# wio_terminal.net
KiCad netlist of a schematic drawn in EAGLE
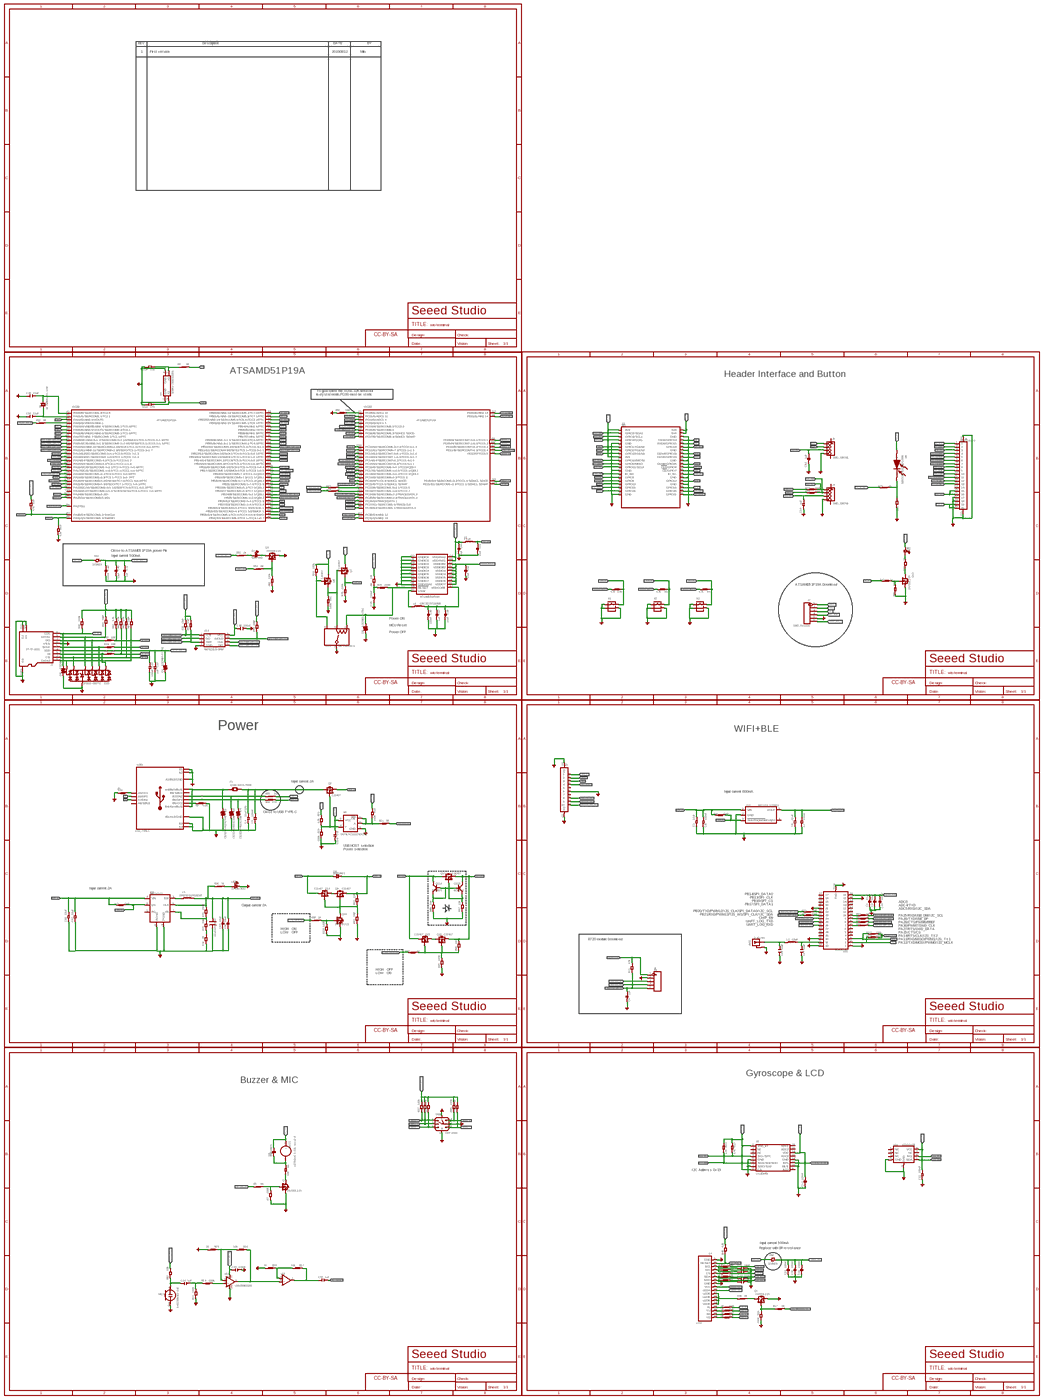
[diagram p0: schematic, sheet 1, overview]
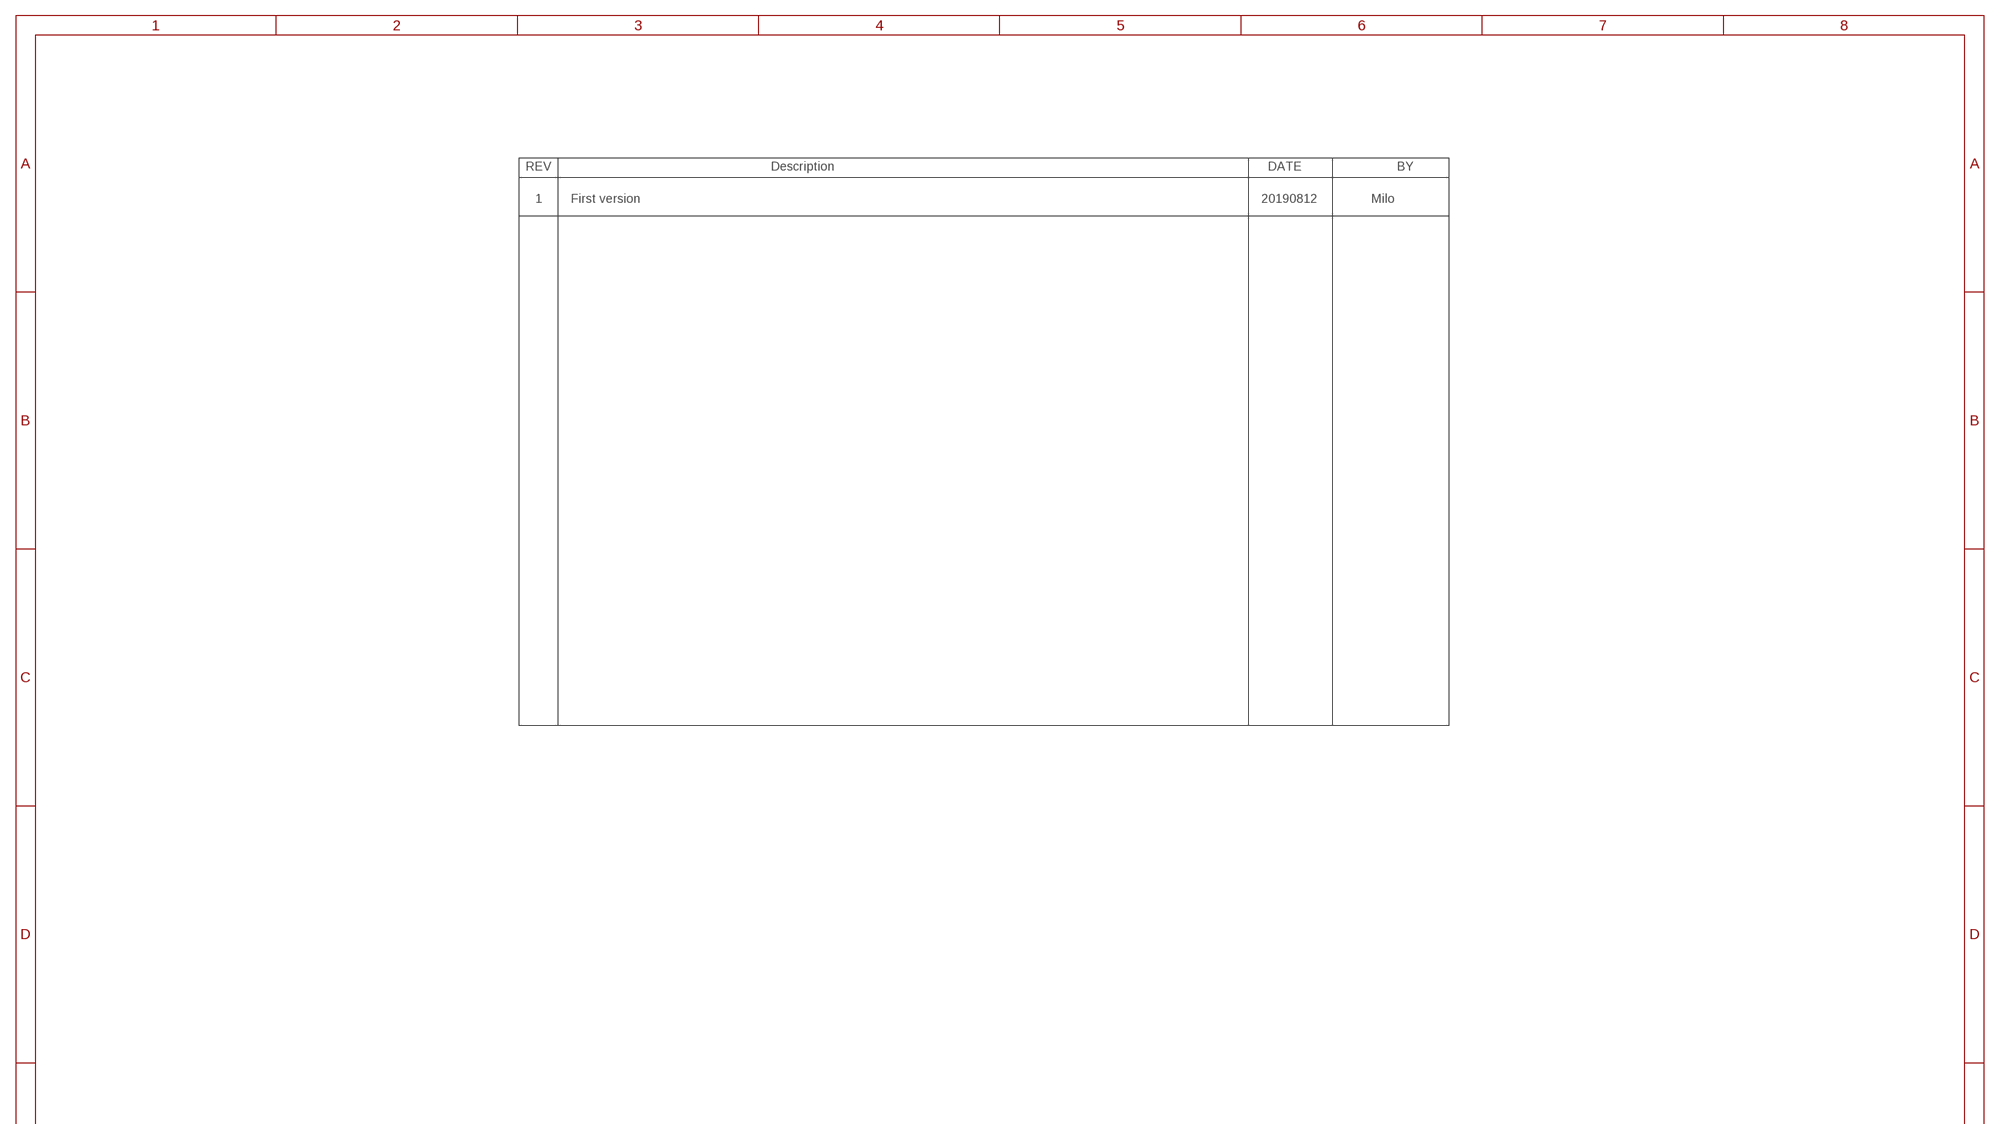
[diagram p1: schematic, sheet 1, part 1 of 7]
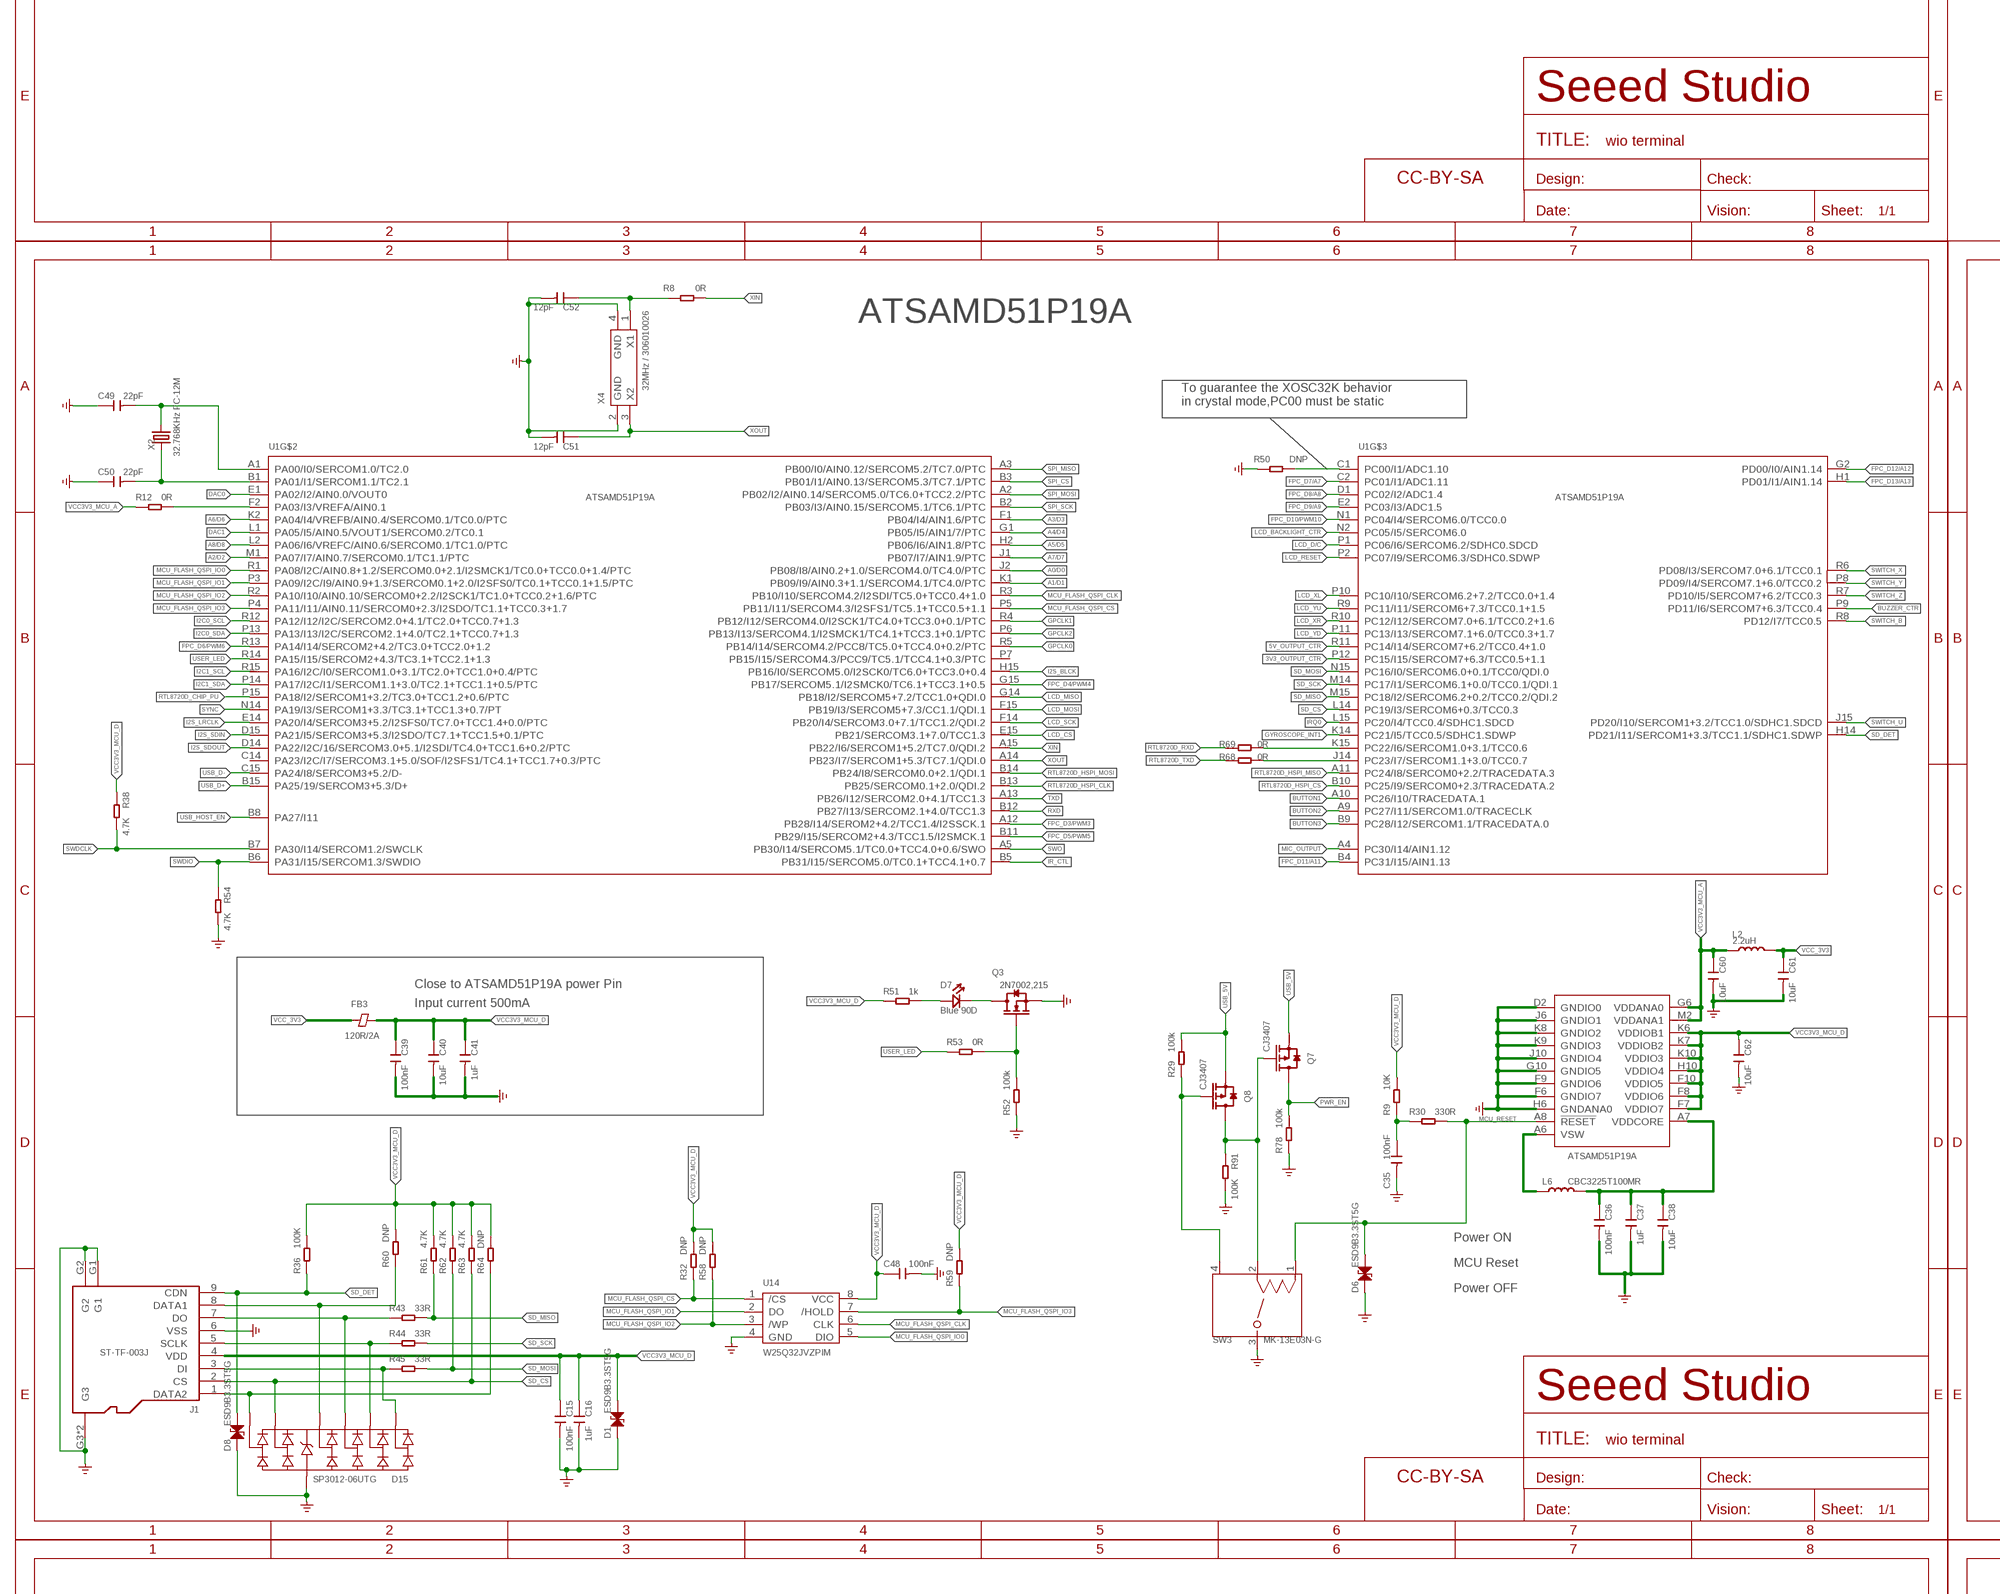
[diagram p2: schematic, sheet 1, part 2 of 7]
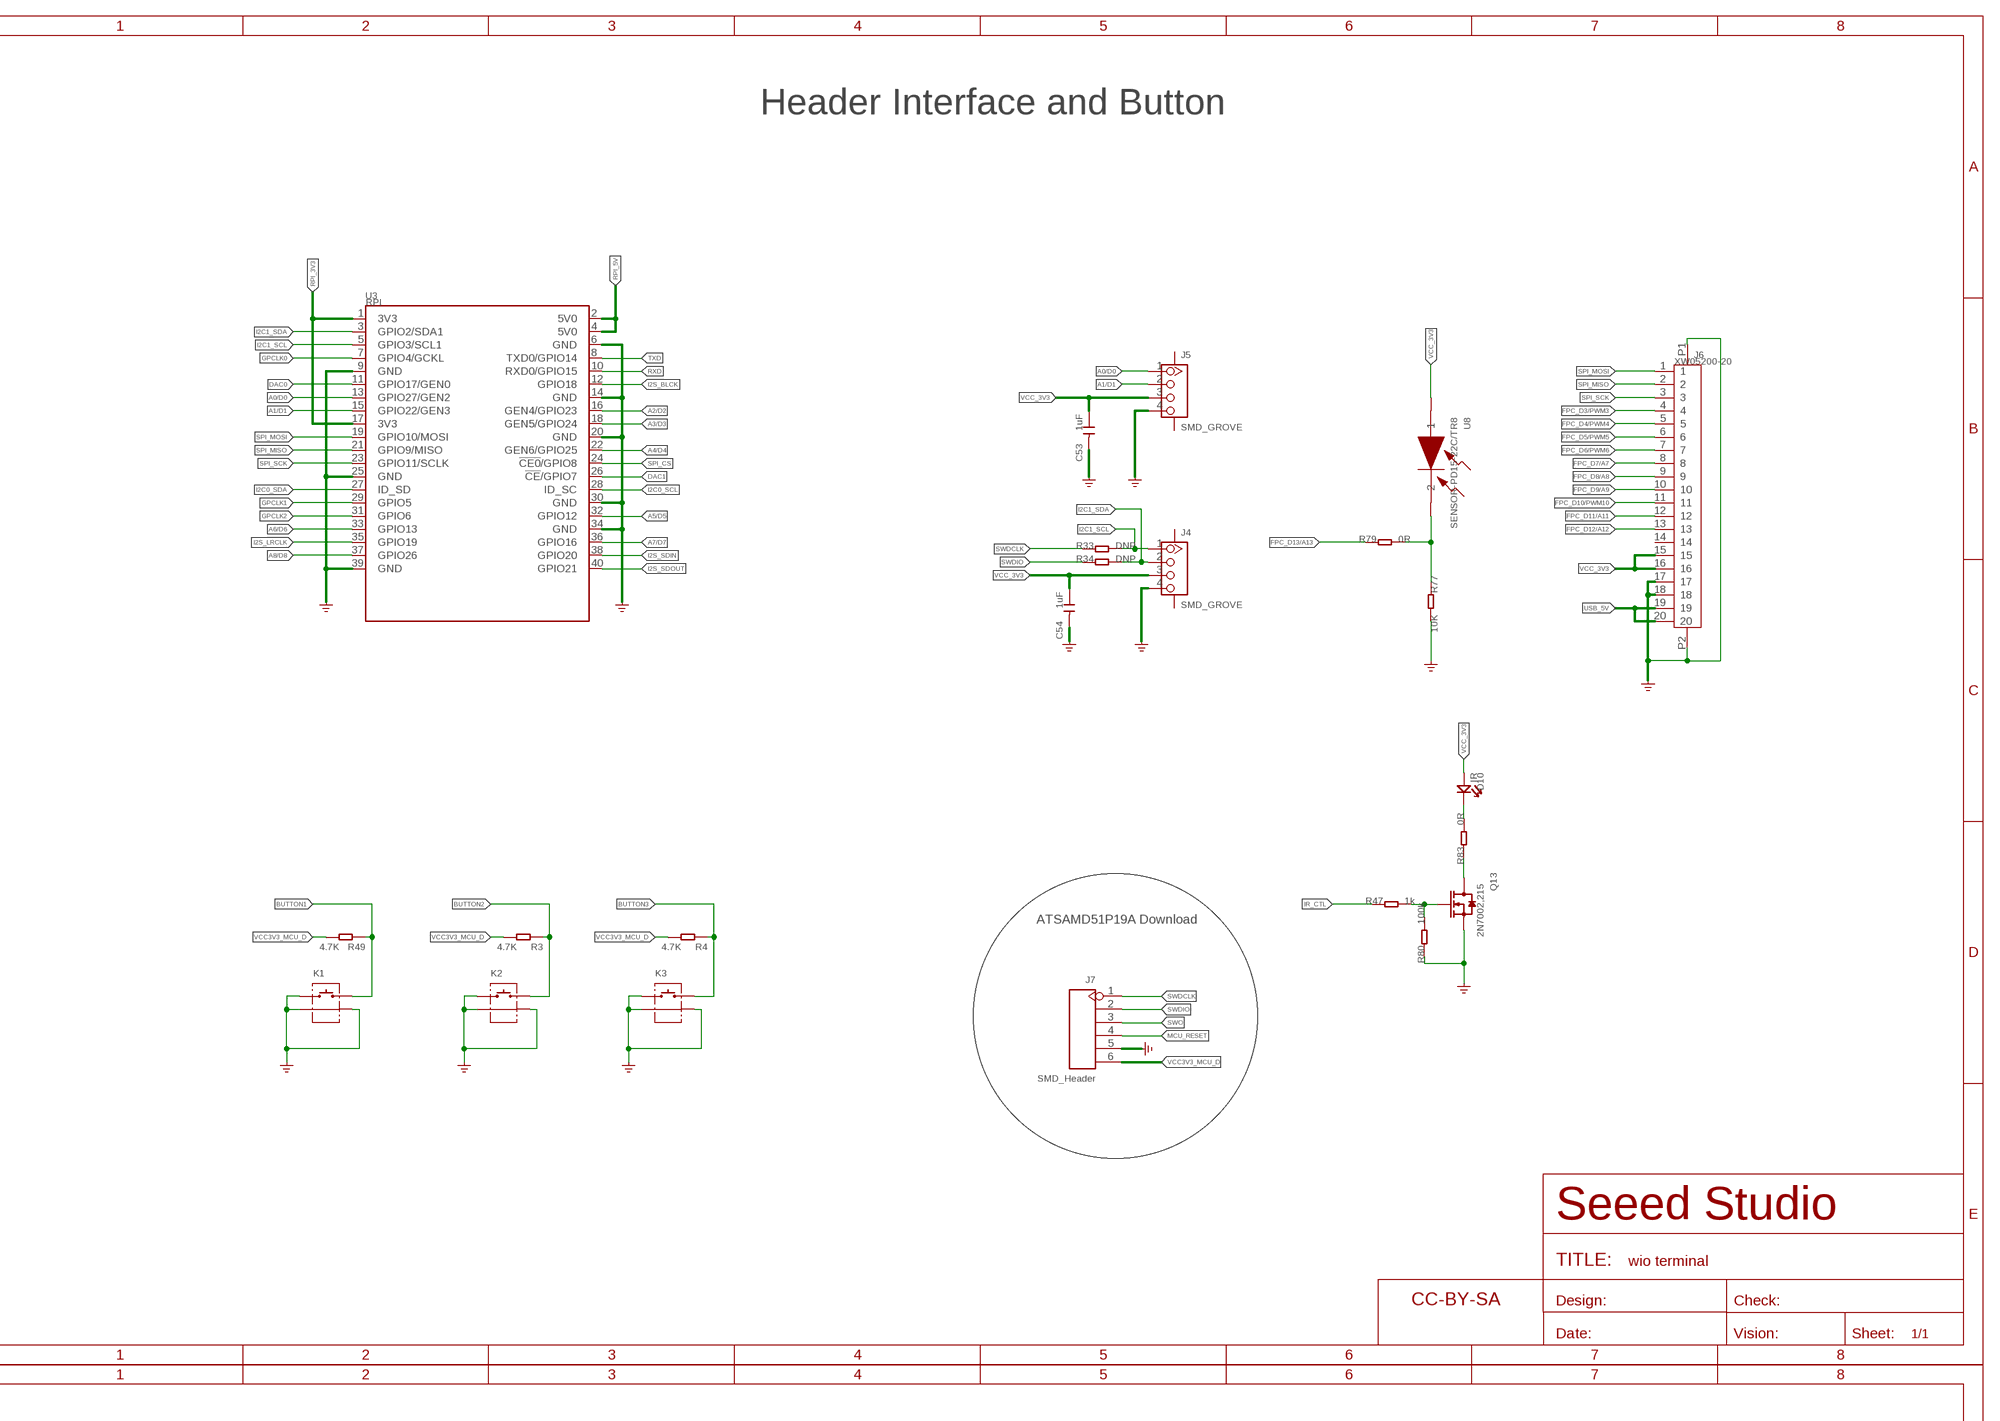
[diagram p3: schematic, sheet 1, part 3 of 7]
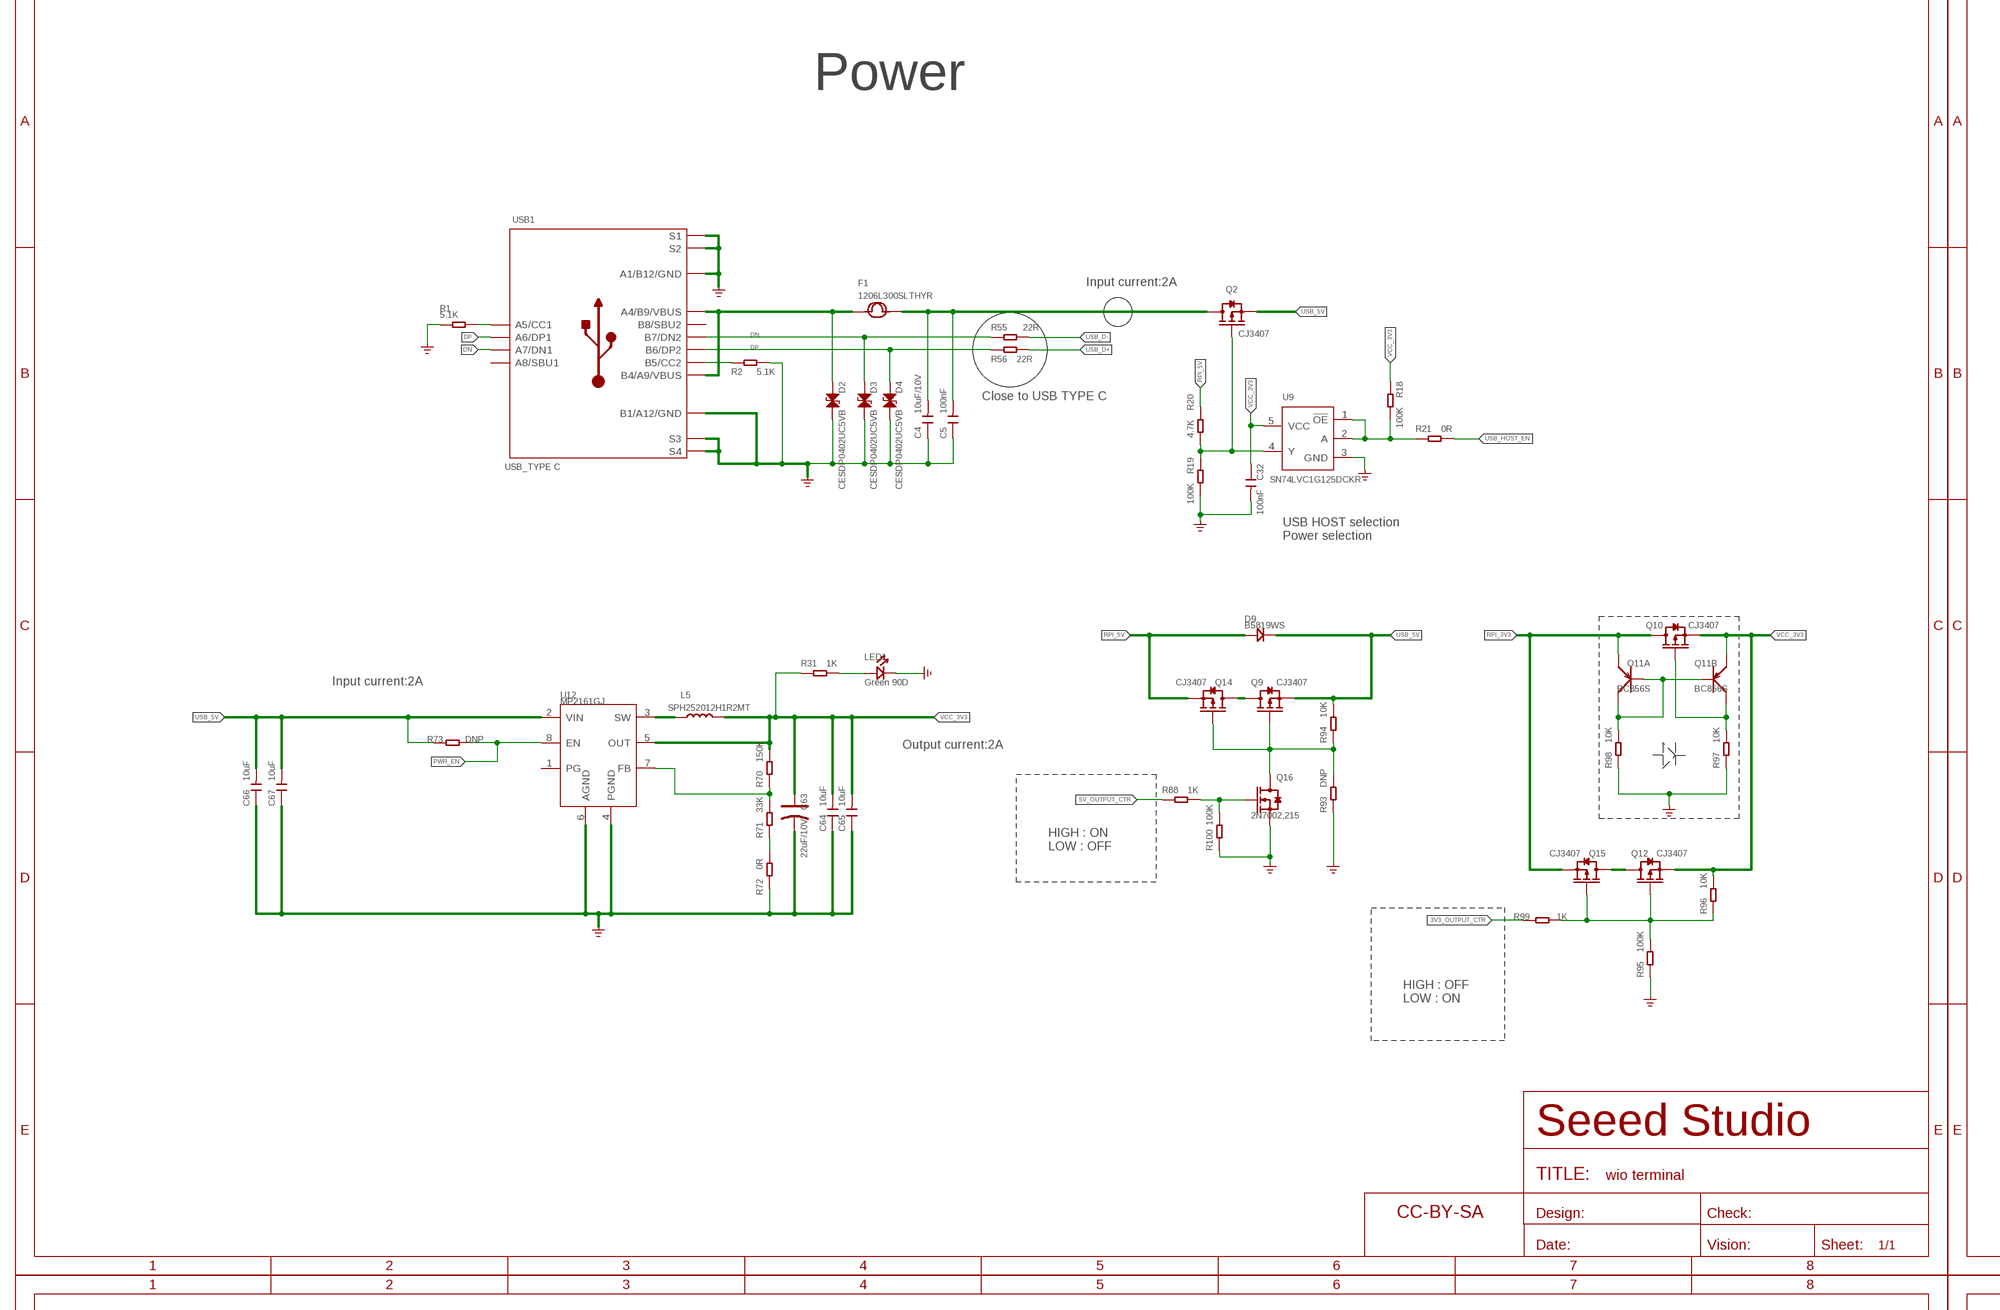
[diagram p4: schematic, sheet 1, part 4 of 7]
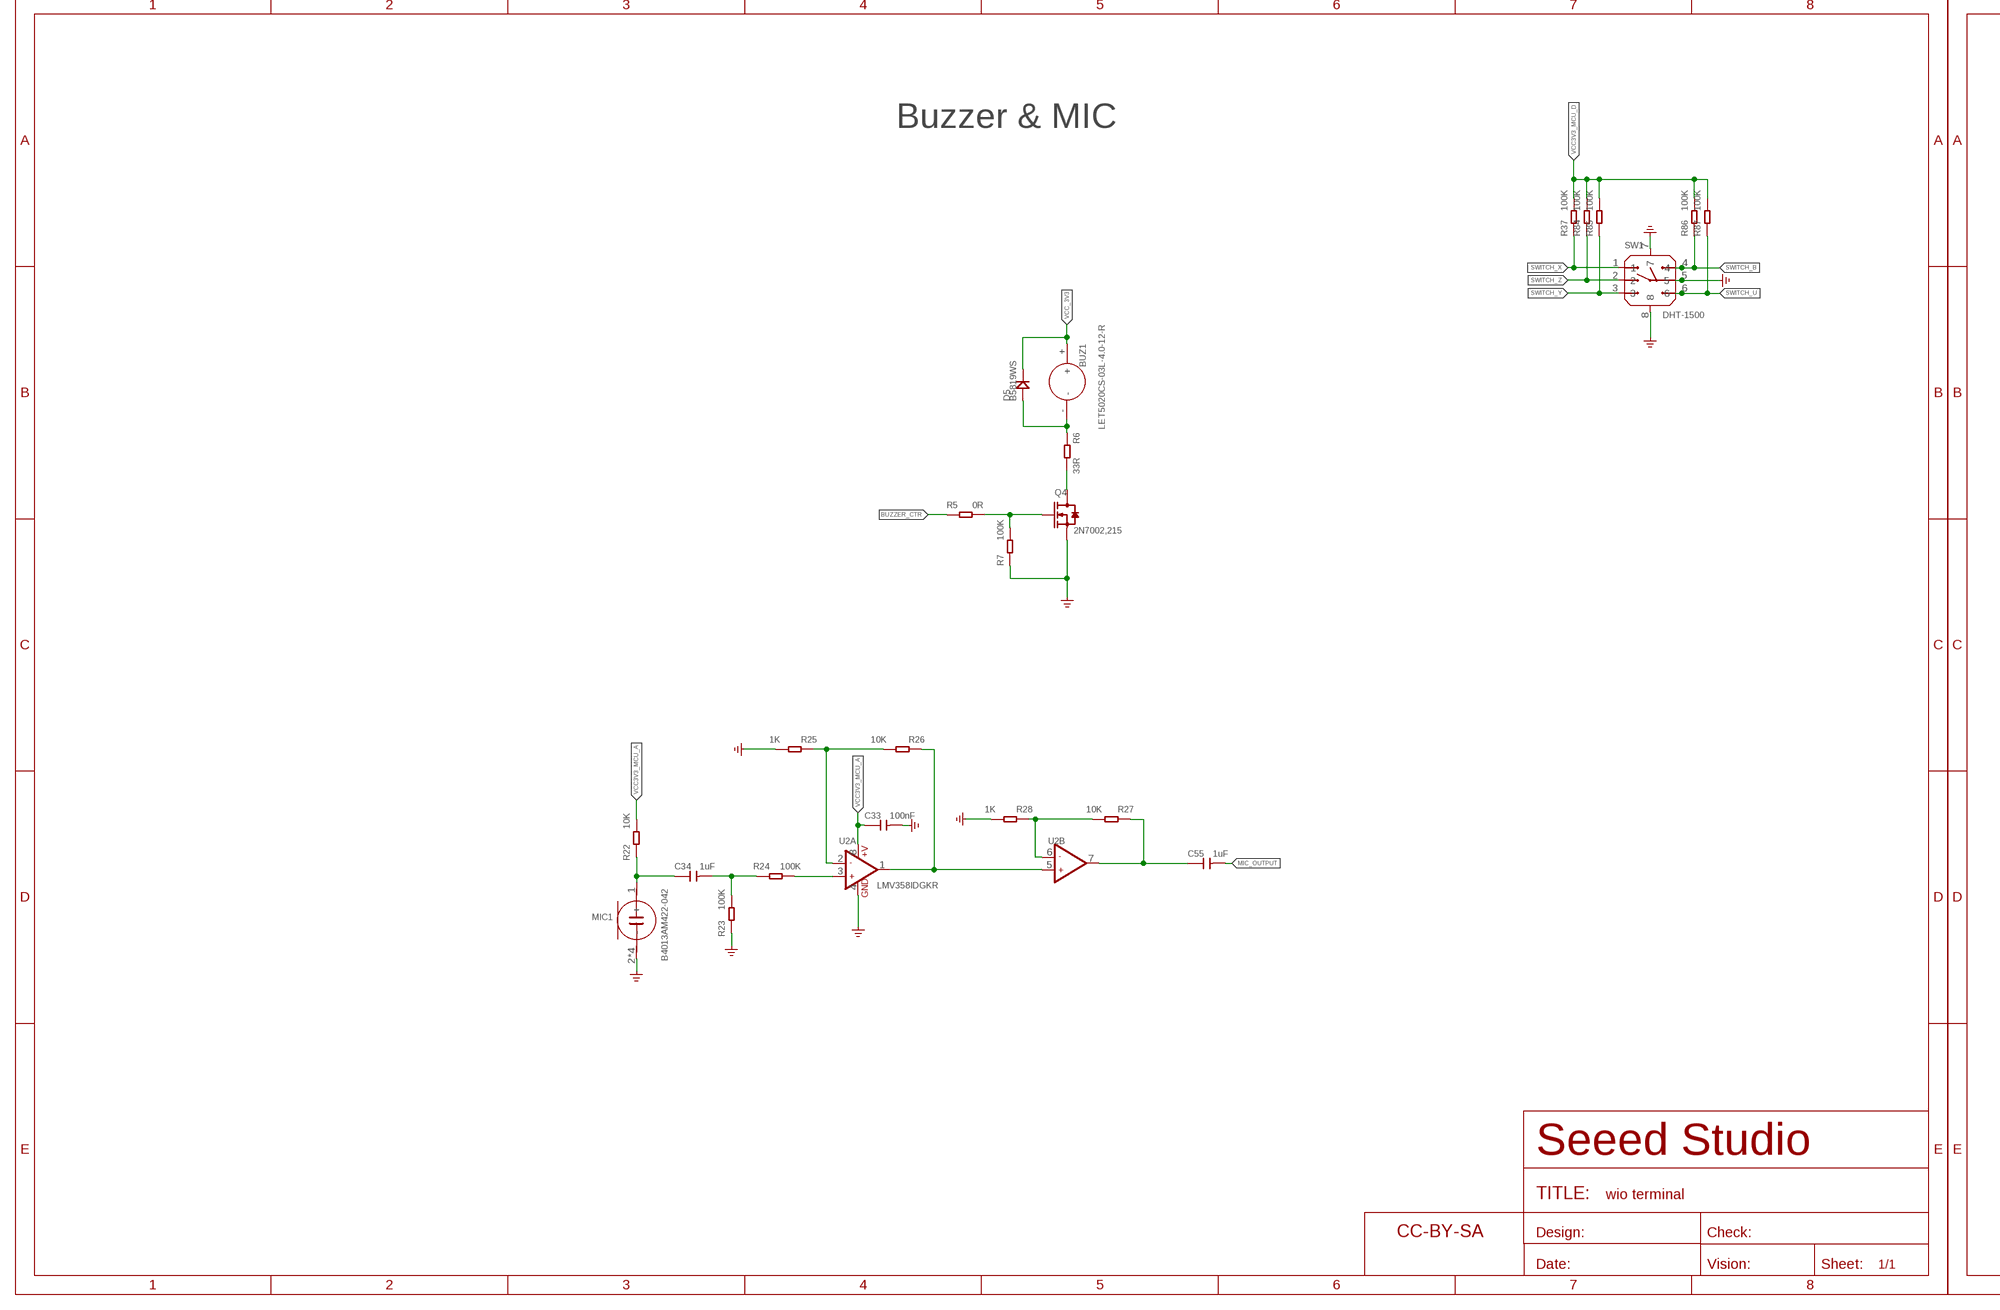
[diagram p5: schematic, sheet 1, part 5 of 7]
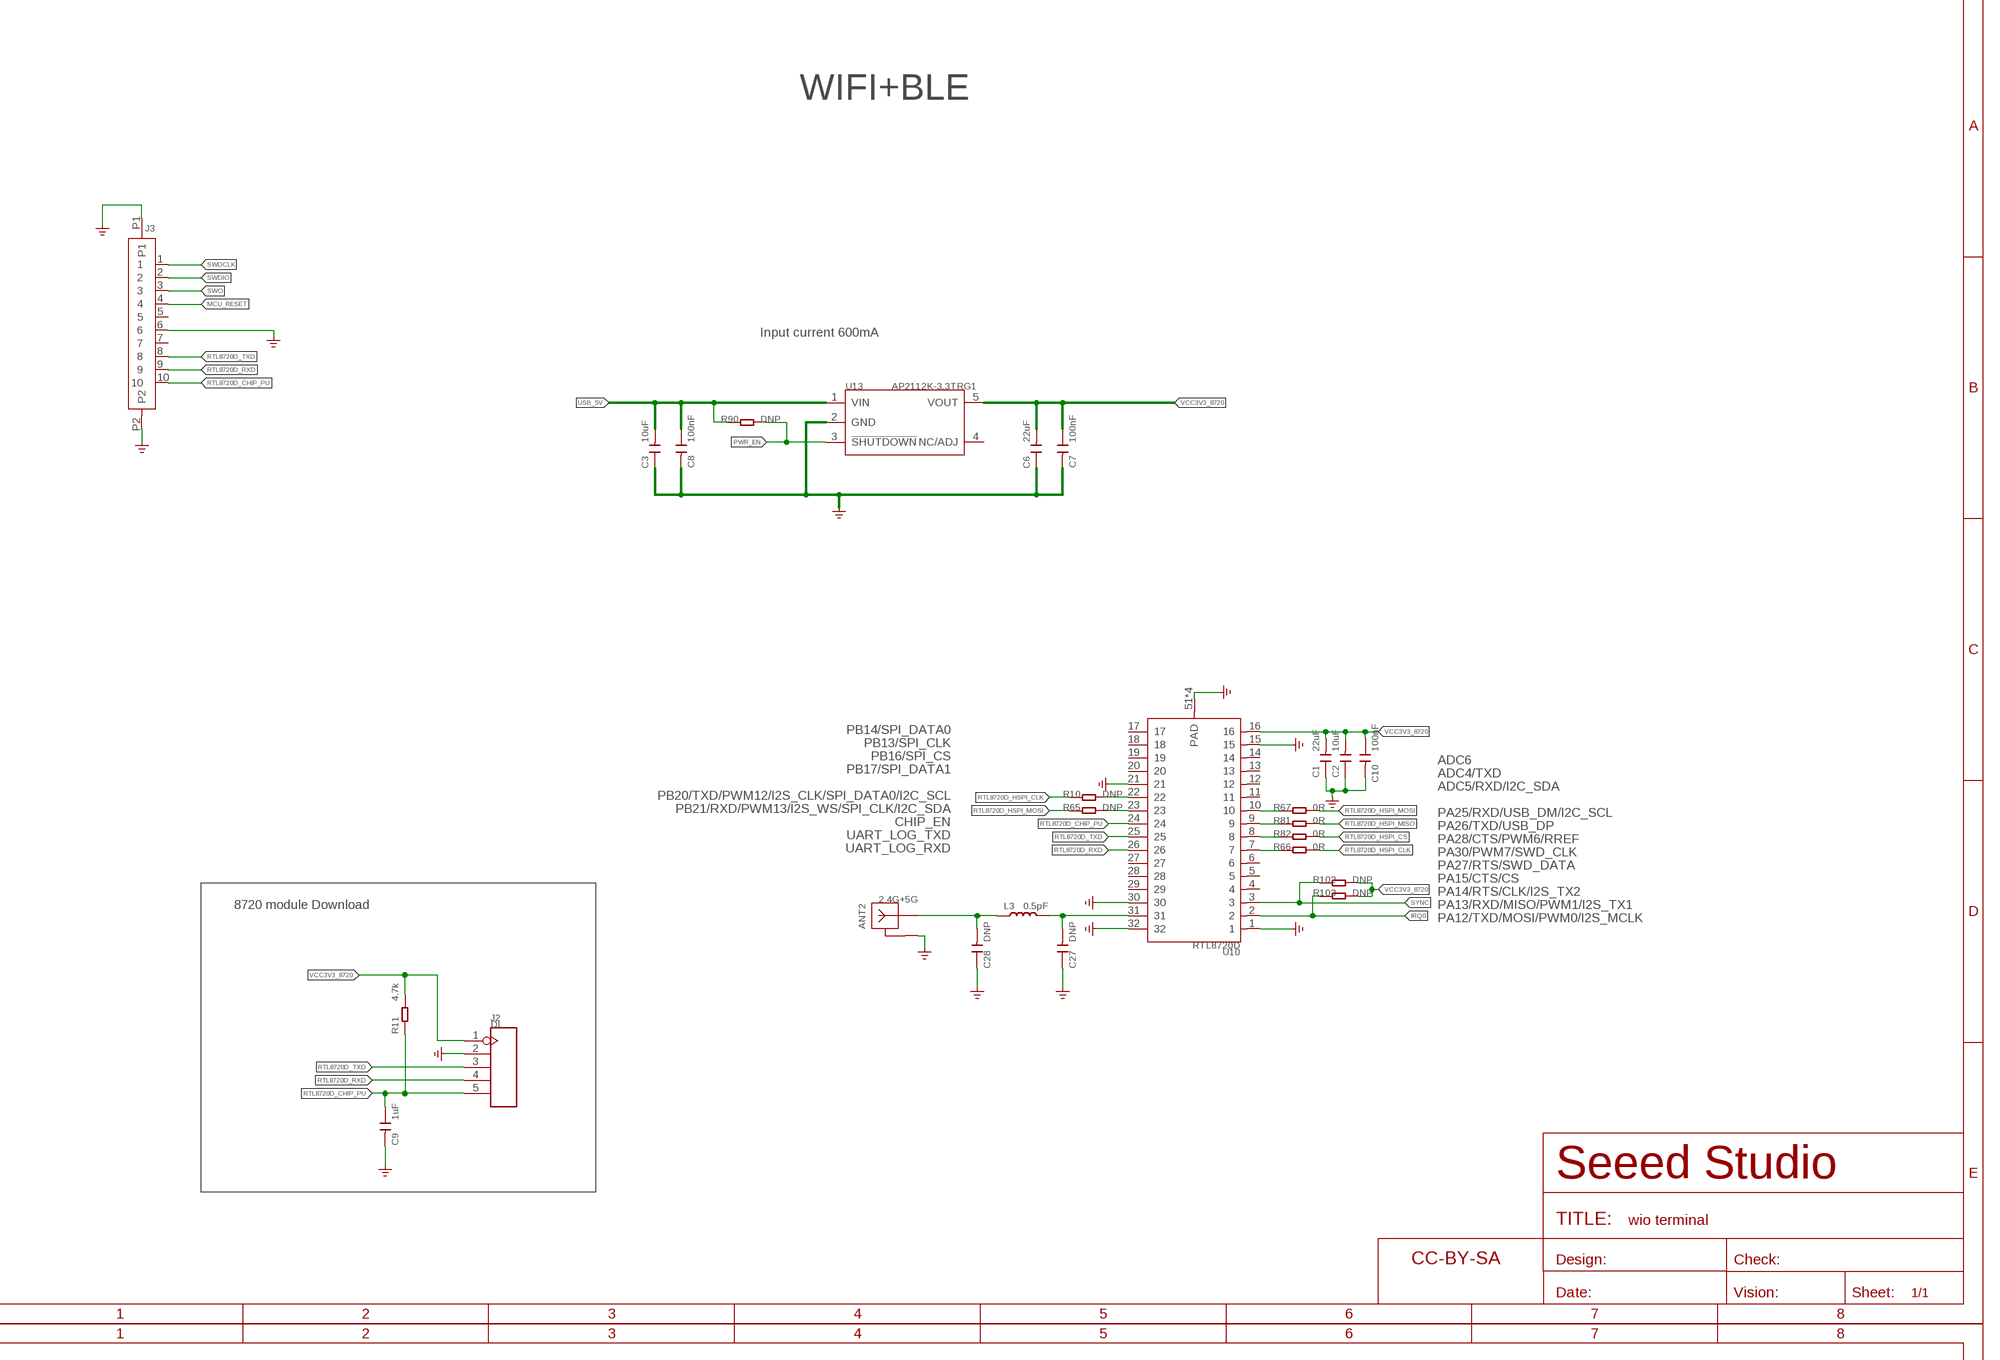
[diagram p6: schematic, sheet 1, part 6 of 7]
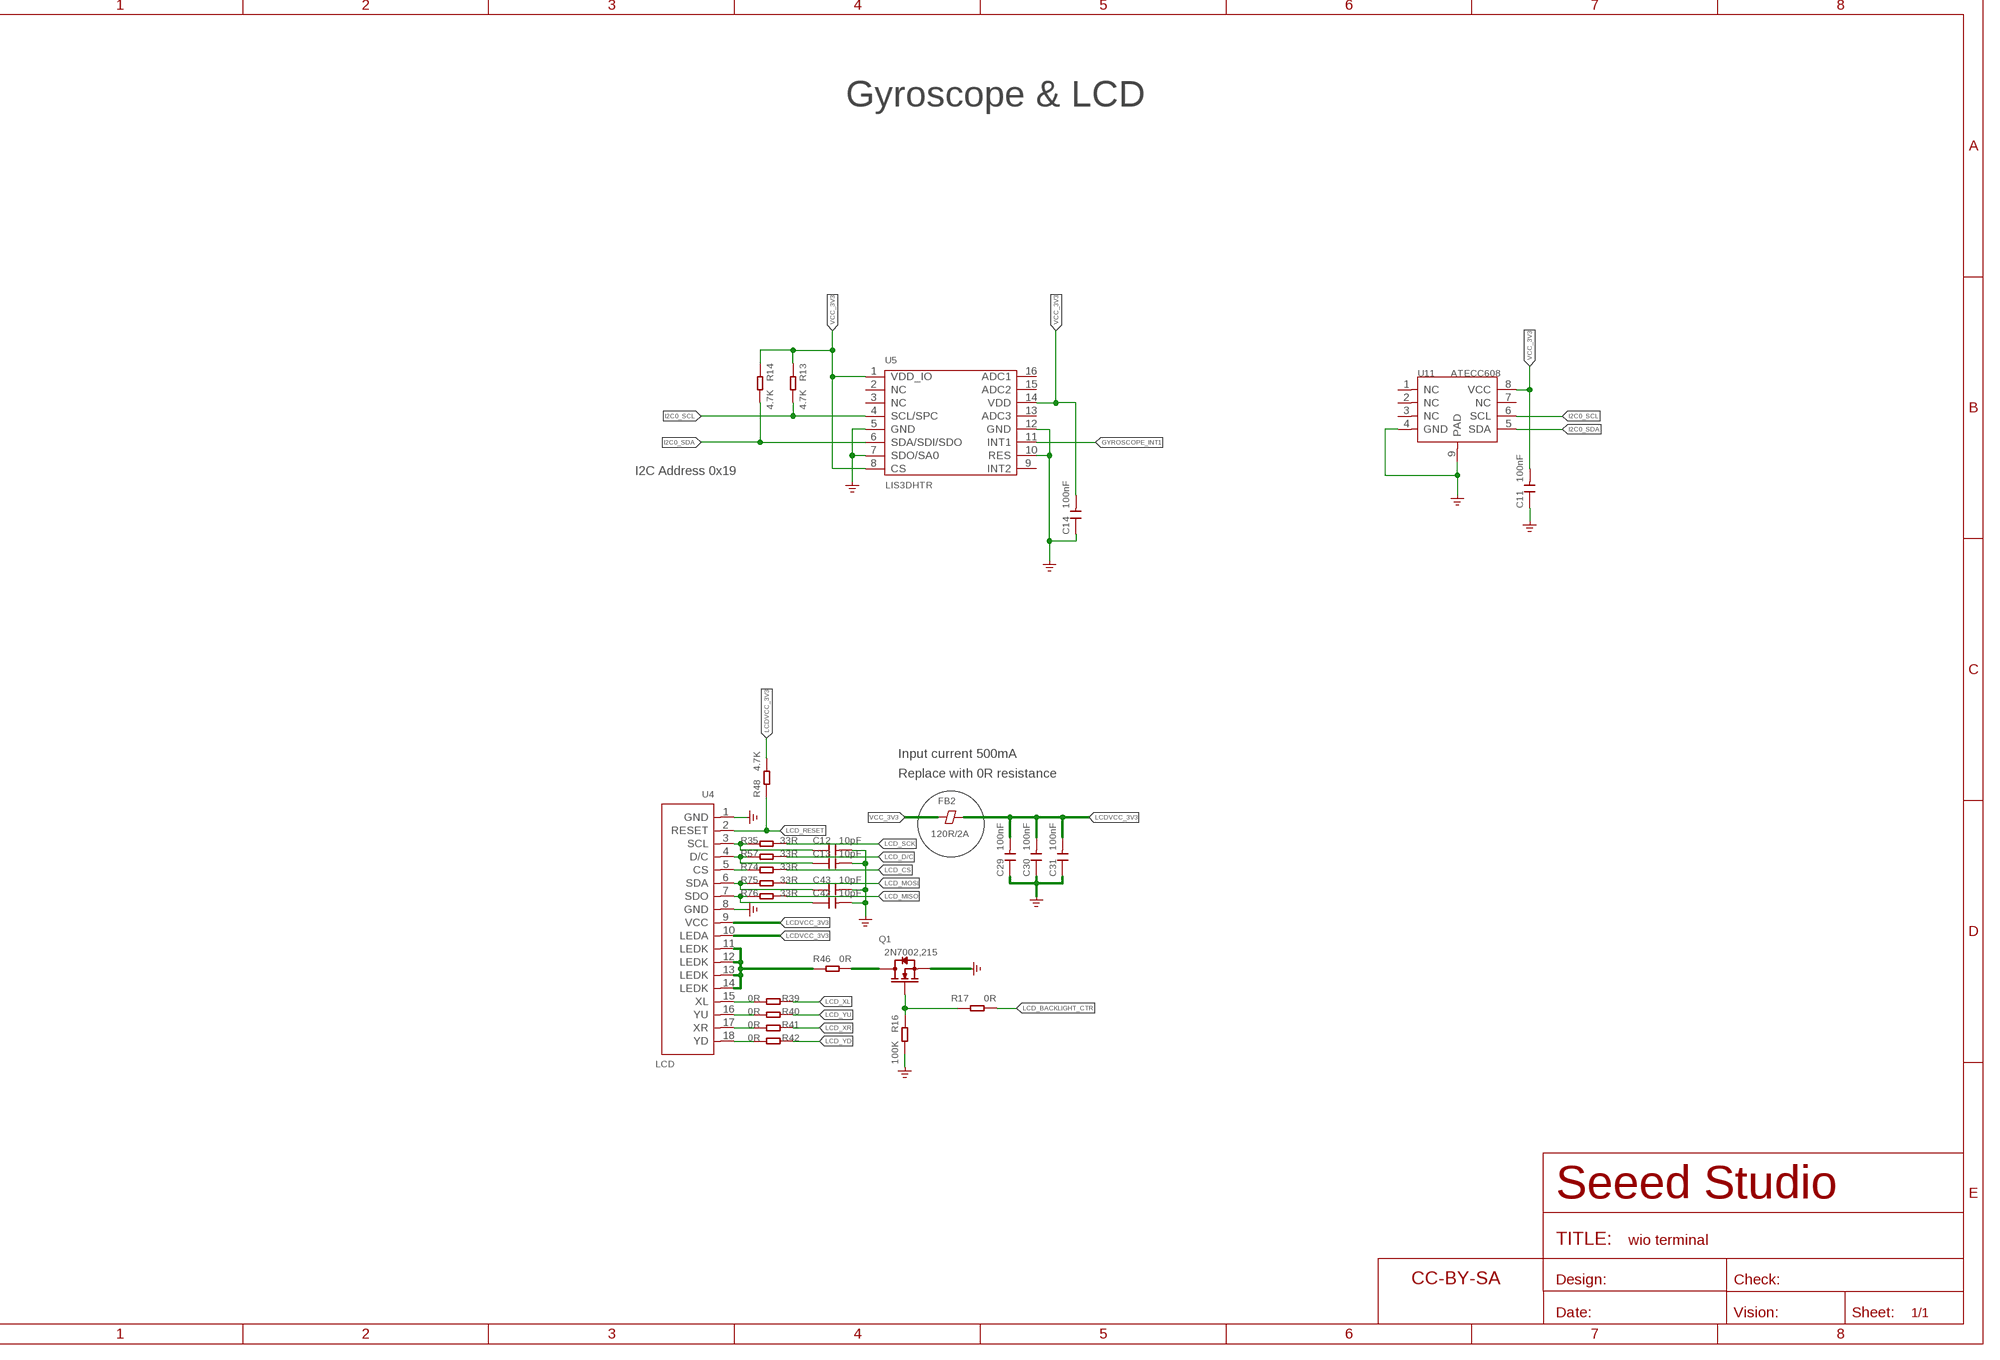
[diagram p7: schematic, sheet 1, part 7 of 7]

(export (version "E")
  (design (tool "Eeschema 10.0.6"))
  (components
    (comp (ref "ANT2")
      (value "2.4G+5G")
      (footprint "eagle-import:ANT2P-AMEBA-D-MODULE")
      (libsource (lib "eagle-import") (part "ANTENNA-2.4G-ANT-AMEBA-D"))
    )
    (comp (ref "BUZ1")
      (value "LET5020CS-03L-4.0-12-R")
      (footprint "eagle-import:BZ3-SMD-5.0X5.0X2.5MM")
      (libsource (lib "eagle-import") (part "BUZZER-312020004"))
    )
    (comp (ref "C1")
      (value "22uF")
      (footprint "eagle-import:C0603")
      (libsource (lib "eagle-import") (part "CAP-0603"))
    )
    (comp (ref "C2")
      (value "10uF")
      (footprint "eagle-import:C0603")
      (libsource (lib "eagle-import") (part "CAP-0603"))
    )
    (comp (ref "C3")
      (value "10uF")
      (footprint "eagle-import:C0603")
      (libsource (lib "eagle-import") (part "CAP-0603"))
    )
    (comp (ref "C4")
      (value "10uF/10V")
      (footprint "eagle-import:C0603")
      (libsource (lib "eagle-import") (part "CAP-0603"))
    )
    (comp (ref "C5")
      (value "100nF")
      (footprint "eagle-import:C0402")
      (libsource (lib "eagle-import") (part "CAP-0402"))
    )
    (comp (ref "C6")
      (value "22uF")
      (footprint "eagle-import:C0603")
      (libsource (lib "eagle-import") (part "CAP-0603"))
    )
    (comp (ref "C7")
      (value "100nF")
      (footprint "eagle-import:C0402")
      (libsource (lib "eagle-import") (part "CAP-0402"))
    )
    (comp (ref "C8")
      (value "100nF")
      (footprint "eagle-import:C0402")
      (libsource (lib "eagle-import") (part "CAP-0402"))
    )
    (comp (ref "C9")
      (value "1uF")
      (footprint "eagle-import:C0402")
      (libsource (lib "eagle-import") (part "CAP-0402"))
    )
    (comp (ref "C10")
      (value "100nF")
      (footprint "eagle-import:C0402")
      (libsource (lib "eagle-import") (part "CAP-0402"))
    )
    (comp (ref "C11")
      (value "100nF")
      (footprint "eagle-import:C0402")
      (libsource (lib "eagle-import") (part "CAP-0402"))
    )
    (comp (ref "C12")
      (value "10pF")
      (footprint "eagle-import:C0402")
      (libsource (lib "eagle-import") (part "CAP-0402"))
    )
    (comp (ref "C13")
      (value "10pF")
      (footprint "eagle-import:C0402")
      (libsource (lib "eagle-import") (part "CAP-0402"))
    )
    (comp (ref "C14")
      (value "100nF")
      (footprint "eagle-import:C0402")
      (libsource (lib "eagle-import") (part "CAP-0402"))
    )
    (comp (ref "C15")
      (value "100nF")
      (footprint "eagle-import:C0402")
      (libsource (lib "eagle-import") (part "CAP-0402"))
    )
    (comp (ref "C16")
      (value "1uF")
      (footprint "eagle-import:C0402")
      (libsource (lib "eagle-import") (part "CAP-0402"))
    )
    (comp (ref "C27")
      (value "DNP")
      (footprint "eagle-import:C0402")
      (libsource (lib "eagle-import") (part "CAP-0402"))
    )
    (comp (ref "C28")
      (value "DNP")
      (footprint "eagle-import:C0402")
      (libsource (lib "eagle-import") (part "CAP-0402"))
    )
    (comp (ref "C29")
      (value "100nF")
      (footprint "eagle-import:C0402")
      (libsource (lib "eagle-import") (part "CAP-0402"))
    )
    (comp (ref "C30")
      (value "100nF")
      (footprint "eagle-import:C0402")
      (libsource (lib "eagle-import") (part "CAP-0402"))
    )
    (comp (ref "C31")
      (value "100nF")
      (footprint "eagle-import:C0402")
      (libsource (lib "eagle-import") (part "CAP-0402"))
    )
    (comp (ref "C32")
      (value "100nF")
      (footprint "eagle-import:C0402")
      (libsource (lib "eagle-import") (part "CAP-0402"))
    )
    (comp (ref "C33")
      (value "100nF")
      (footprint "eagle-import:C0402")
      (libsource (lib "eagle-import") (part "CAP-0402"))
    )
    (comp (ref "C34")
      (value "1uF")
      (footprint "eagle-import:C0402")
      (libsource (lib "eagle-import") (part "CAP-0402"))
    )
    (comp (ref "C35")
      (value "100nF")
      (footprint "eagle-import:C0402")
      (libsource (lib "eagle-import") (part "CAP-0402"))
    )
    (comp (ref "C36")
      (value "100nF")
      (footprint "eagle-import:C0402")
      (libsource (lib "eagle-import") (part "CAP-0402"))
    )
    (comp (ref "C37")
      (value "1uF")
      (footprint "eagle-import:C0402")
      (libsource (lib "eagle-import") (part "CAP-0402"))
    )
    (comp (ref "C38")
      (value "10uF")
      (footprint "eagle-import:C0402")
      (libsource (lib "eagle-import") (part "CAP-0402"))
    )
    (comp (ref "C39")
      (value "100nF")
      (footprint "eagle-import:C0402")
      (libsource (lib "eagle-import") (part "CAP-0402"))
    )
    (comp (ref "C40")
      (value "10uF")
      (footprint "eagle-import:C0402")
      (libsource (lib "eagle-import") (part "CAP-0402"))
    )
    (comp (ref "C41")
      (value "1uF")
      (footprint "eagle-import:C0402")
      (libsource (lib "eagle-import") (part "CAP-0402"))
    )
    (comp (ref "C42")
      (value "10pF")
      (footprint "eagle-import:C0402")
      (libsource (lib "eagle-import") (part "CAP-0402"))
    )
    (comp (ref "C43")
      (value "10pF")
      (footprint "eagle-import:C0402")
      (libsource (lib "eagle-import") (part "CAP-0402"))
    )
    (comp (ref "C48")
      (value "100nF")
      (footprint "eagle-import:C0402")
      (libsource (lib "eagle-import") (part "CAP-0402"))
    )
    (comp (ref "C49")
      (value "22pF")
      (footprint "eagle-import:C0402")
      (libsource (lib "eagle-import") (part "CAP-0402"))
    )
    (comp (ref "C50")
      (value "22pF")
      (footprint "eagle-import:C0402")
      (libsource (lib "eagle-import") (part "CAP-0402"))
    )
    (comp (ref "C51")
      (value "12pF")
      (footprint "eagle-import:C0402")
      (libsource (lib "eagle-import") (part "CAP-0402"))
    )
    (comp (ref "C52")
      (value "12pF")
      (footprint "eagle-import:C0402")
      (libsource (lib "eagle-import") (part "CAP-0402"))
    )
    (comp (ref "C53")
      (value "1uF")
      (footprint "eagle-import:C0402")
      (libsource (lib "eagle-import") (part "CAP-0402"))
    )
    (comp (ref "C54")
      (value "1uF")
      (footprint "eagle-import:C0402")
      (libsource (lib "eagle-import") (part "CAP-0402"))
    )
    (comp (ref "C55")
      (value "1uF")
      (footprint "eagle-import:C0402")
      (libsource (lib "eagle-import") (part "CAP-0402"))
    )
    (comp (ref "C60")
      (value "10uF")
      (footprint "eagle-import:C0402")
      (libsource (lib "eagle-import") (part "CAP-0402"))
    )
    (comp (ref "C61")
      (value "10uF")
      (footprint "eagle-import:C0402")
      (libsource (lib "eagle-import") (part "CAP-0402"))
    )
    (comp (ref "C62")
      (value "10uF")
      (footprint "eagle-import:C0402")
      (libsource (lib "eagle-import") (part "CAP-0402"))
    )
    (comp (ref "C63")
      (value "22uF/10V")
      (footprint "eagle-import:AVX-A")
      (libsource (lib "eagle-import") (part "CAP-POLAR-AVX-A"))
    )
    (comp (ref "C64")
      (value "10uF")
      (footprint "eagle-import:C0402")
      (libsource (lib "eagle-import") (part "CAP-0402"))
    )
    (comp (ref "C65")
      (value "10uF")
      (footprint "eagle-import:C0402")
      (libsource (lib "eagle-import") (part "CAP-0402"))
    )
    (comp (ref "C66")
      (value "10uF")
      (footprint "eagle-import:C0402")
      (libsource (lib "eagle-import") (part "CAP-0402"))
    )
    (comp (ref "C67")
      (value "10uF")
      (footprint "eagle-import:C0402")
      (libsource (lib "eagle-import") (part "CAP-0402"))
    )
    (comp (ref "D1")
      (value "ESD9B3.3ST5G")
      (footprint "eagle-import:ESD-0402")
      (libsource (lib "eagle-import") (part "D-ESD-2P-DOUBLE-0402"))
    )
    (comp (ref "D2")
      (value "CESDP0402UC5VB")
      (footprint "eagle-import:ESD-0402")
      (libsource (lib "eagle-import") (part "D-ESD-2P-DOUBLE-0402"))
    )
    (comp (ref "D3")
      (value "CESDP0402UC5VB")
      (footprint "eagle-import:ESD-0402")
      (libsource (lib "eagle-import") (part "D-ESD-2P-DOUBLE-0402"))
    )
    (comp (ref "D4")
      (value "CESDP0402UC5VB")
      (footprint "eagle-import:ESD-0402")
      (libsource (lib "eagle-import") (part "D-ESD-2P-DOUBLE-0402"))
    )
    (comp (ref "D5")
      (value "B5819WS")
      (footprint "eagle-import:SOD-323")
      (libsource (lib "eagle-import") (part "DIODE'0805'"))
    )
    (comp (ref "D6")
      (value "ESD9B3.3ST5G")
      (footprint "eagle-import:ESD-0402")
      (libsource (lib "eagle-import") (part "D-ESD-2P-DOUBLE-0402"))
    )
    (comp (ref "D7")
      (value "Blue 90D")
      (footprint "eagle-import:LED-SIDE-VIEW-0603-RIGHT")
      (libsource (lib "eagle-import") (part "LED'RIGHT'"))
    )
    (comp (ref "D8")
      (value "ESD9B3.3ST5G")
      (footprint "eagle-import:ESD-0402")
      (libsource (lib "eagle-import") (part "D-ESD-2P-DOUBLE-0402"))
    )
    (comp (ref "D9")
      (value "B5819WS")
      (footprint "eagle-import:SOD-323")
      (libsource (lib "eagle-import") (part "DIODE'0805'"))
    )
    (comp (ref "D10")
      (value "IR")
      (footprint "eagle-import:LED-0603")
      (libsource (lib "eagle-import") (part "LED'0603'"))
    )
    (comp (ref "D15")
      (value "SP3012-06UTG")
      (footprint "eagle-import:UDFN14-0.5-3.5X1.35X0.5MM")
      (libsource (lib "eagle-import") (part "D-ESD-14P"))
    )
    (comp (ref "F1")
      (value "1206L300SLTHYR")
      (footprint "eagle-import:F1206")
      (libsource (lib "eagle-import") (part "FUSE'1206'"))
    )
    (comp (ref "FB2")
      (value "120R/2A")
      (footprint "eagle-import:F0402")
      (libsource (lib "eagle-import") (part "FERRITE-BEAD-0402"))
    )
    (comp (ref "FB3")
      (value "120R/2A")
      (footprint "eagle-import:F0402")
      (libsource (lib "eagle-import") (part "FERRITE-BEAD-0402"))
    )
    (comp (ref "J1")
      (value "ST-TF-003J")
      (footprint "eagle-import:MICRO-SD9+4P-SMD-16.1X14.5X1.85MM")
      (libsource (lib "eagle-import") (part "MICRO-SD-CARD-HOLDER-9P-320090000"))
    )
    (comp (ref "J2")
      (value "DL")
      (footprint "eagle-import:H5-SMD-2.0-TEST")
      (libsource (lib "eagle-import") (part "HEADER-5P-TEST"))
    )
    (comp (ref "J3")
      (value "FPC-CONNECTOR-10PTOP''")
      (footprint "eagle-import:FPC10-SMD-0.5-10.6X3.5X4.5MM")
      (libsource (lib "eagle-import") (part "FPC-CONNECTOR-10PTOP''"))
    )
    (comp (ref "J4")
      (value "SMD_GROVE")
      (footprint "eagle-import:HW4-SMD-2.0-90D")
      (libsource (lib "eagle-import") (part "GROVE-CONNECTOR-SMD-320110032"))
    )
    (comp (ref "J5")
      (value "SMD_GROVE")
      (footprint "eagle-import:HW4-SMD-2.0-90D")
      (libsource (lib "eagle-import") (part "GROVE-CONNECTOR-SMD-320110032"))
    )
    (comp (ref "J6")
      (value "XW05200-20")
      (footprint "eagle-import:FPC20-SMD-0.5-90D")
      (libsource (lib "eagle-import") (part "FPC-CONNECTOR-20P"))
    )
    (comp (ref "J7")
      (value "SMD_Header")
      (footprint "eagle-import:H6-SMD-2.0_TEST")
      (libsource (lib "eagle-import") (part "HEADER-6P-2.0-TEST"))
    )
    (comp (ref "K1")
      (value "BUTTON-2+2P-TS-1073B")
      (footprint "eagle-import:SW2+2P-3.45-4.8X2.5X1.8MM")
      (libsource (lib "eagle-import") (part "BUTTON-2+2P-TS-1073B"))
    )
    (comp (ref "K2")
      (value "BUTTON-2+2P-TS-1073B")
      (footprint "eagle-import:SW2+2P-3.45-4.8X2.5X1.8MM")
      (libsource (lib "eagle-import") (part "BUTTON-2+2P-TS-1073B"))
    )
    (comp (ref "K3")
      (value "BUTTON-2+2P-TS-1073B")
      (footprint "eagle-import:SW2+2P-3.45-4.8X2.5X1.8MM")
      (libsource (lib "eagle-import") (part "BUTTON-2+2P-TS-1073B"))
    )
    (comp (ref "L2")
      (value "2.2uH")
      (footprint "eagle-import:L0805")
      (libsource (lib "eagle-import") (part "INDUCTOR'0805'"))
    )
    (comp (ref "L3")
      (value "0.5pF")
      (footprint "eagle-import:L0402")
      (libsource (lib "eagle-import") (part "INDUCTOR'0402'"))
    )
    (comp (ref "L5")
      (value "SPH252012H1R2MT")
      (footprint "eagle-import:L2520")
      (libsource (lib "eagle-import") (part "INDUCTOR-2520"))
    )
    (comp (ref "L6")
      (value "CBC3225T100MR")
      (footprint "eagle-import:L2520")
      (libsource (lib "eagle-import") (part "INDUCTOR-2520"))
    )
    (comp (ref "LED1")
      (value "Green 90D")
      (footprint "eagle-import:LED-SIDE-VIEW-0603-RIGHT")
      (libsource (lib "eagle-import") (part "LED'RIGHT'"))
    )
    (comp (ref "MIC1")
      (value "B4013AM422-042")
      (footprint "eagle-import:MIC2-SMD-4X4MM")
      (libsource (lib "eagle-import") (part "MIC2P-B4013AM422-042"))
    )
    (comp (ref "Q1")
      (value "2N7002,215")
      (footprint "eagle-import:SOT-23")
      (libsource (lib "eagle-import") (part "MOSFET-N'SOT23'"))
    )
    (comp (ref "Q2")
      (value "CJ3407")
      (footprint "eagle-import:SOT-23")
      (libsource (lib "eagle-import") (part "MOSFET-P'SI2323CDS/SI2305DS{lt}BR{gt}'"))
    )
    (comp (ref "Q3")
      (value "2N7002,215")
      (footprint "eagle-import:SOT-23")
      (libsource (lib "eagle-import") (part "MOSFET-N'SOT23'"))
    )
    (comp (ref "Q4")
      (value "2N7002,215")
      (footprint "eagle-import:SOT-23")
      (libsource (lib "eagle-import") (part "MOSFET-N'SOT23'"))
    )
    (comp (ref "Q7")
      (value "CJ3407")
      (footprint "eagle-import:SOT-23")
      (libsource (lib "eagle-import") (part "MOSFET-P'SI2323CDS/SI2305DS{lt}BR{gt}'"))
    )
    (comp (ref "Q8")
      (value "CJ3407")
      (footprint "eagle-import:SOT-23")
      (libsource (lib "eagle-import") (part "MOSFET-P'SI2323CDS/SI2305DS{lt}BR{gt}'"))
    )
    (comp (ref "Q9")
      (value "CJ3407")
      (footprint "eagle-import:SOT-23")
      (libsource (lib "eagle-import") (part "MOSFET-P'SI2323CDS/SI2305DS{lt}BR{gt}'"))
    )
    (comp (ref "Q10")
      (value "CJ3407")
      (footprint "eagle-import:SOT-23")
      (libsource (lib "eagle-import") (part "MOSFET-P'SI2323CDS/SI2305DS{lt}BR{gt}'"))
    )
    (comp (ref "Q11")
      (value "BC856S")
      (footprint "eagle-import:SOT-363")
      (libsource (lib "eagle-import") (part "TRANSISTOR-DUAL-PNP-SC-88"))
    )
    (comp (ref "Q12")
      (value "CJ3407")
      (footprint "eagle-import:SOT-23")
      (libsource (lib "eagle-import") (part "MOSFET-P'SI2323CDS/SI2305DS{lt}BR{gt}'"))
    )
    (comp (ref "Q13")
      (value "2N7002,215")
      (footprint "eagle-import:SOT-23")
      (libsource (lib "eagle-import") (part "MOSFET-N'SOT23'"))
    )
    (comp (ref "Q14")
      (value "CJ3407")
      (footprint "eagle-import:SOT-23")
      (libsource (lib "eagle-import") (part "MOSFET-P'SI2323CDS/SI2305DS{lt}BR{gt}'"))
    )
    (comp (ref "Q15")
      (value "CJ3407")
      (footprint "eagle-import:SOT-23")
      (libsource (lib "eagle-import") (part "MOSFET-P'SI2323CDS/SI2305DS{lt}BR{gt}'"))
    )
    (comp (ref "Q16")
      (value "2N7002,215")
      (footprint "eagle-import:SOT-23")
      (libsource (lib "eagle-import") (part "MOSFET-N'SOT23'"))
    )
    (comp (ref "R1")
      (value "5.1K")
      (footprint "eagle-import:R0402")
      (libsource (lib "eagle-import") (part "RES-0402"))
    )
    (comp (ref "R2")
      (value "5.1K")
      (footprint "eagle-import:R0402")
      (libsource (lib "eagle-import") (part "RES-0402"))
    )
    (comp (ref "R3")
      (value "4.7K")
      (footprint "eagle-import:R0402")
      (libsource (lib "eagle-import") (part "RES-0402"))
    )
    (comp (ref "R4")
      (value "4.7K")
      (footprint "eagle-import:R0402")
      (libsource (lib "eagle-import") (part "RES-0402"))
    )
    (comp (ref "R5")
      (value "0R")
      (footprint "eagle-import:R0402")
      (libsource (lib "eagle-import") (part "RES-0402"))
    )
    (comp (ref "R6")
      (value "33R")
      (footprint "eagle-import:R0402")
      (libsource (lib "eagle-import") (part "RES-0402"))
    )
    (comp (ref "R7")
      (value "100K")
      (footprint "eagle-import:R0402")
      (libsource (lib "eagle-import") (part "RES-0402"))
    )
    (comp (ref "R8")
      (value "0R")
      (footprint "eagle-import:R0402")
      (libsource (lib "eagle-import") (part "RES-0402"))
    )
    (comp (ref "R9")
      (value "10K")
      (footprint "eagle-import:R0402")
      (libsource (lib "eagle-import") (part "RES-0402"))
    )
    (comp (ref "R10")
      (value "DNP")
      (footprint "eagle-import:R0402")
      (libsource (lib "eagle-import") (part "RES-0402"))
    )
    (comp (ref "R11")
      (value "4.7k")
      (footprint "eagle-import:R0402")
      (libsource (lib "eagle-import") (part "RES-0402"))
    )
    (comp (ref "R12")
      (value "0R")
      (footprint "eagle-import:R0402")
      (libsource (lib "eagle-import") (part "RES-0402"))
    )
    (comp (ref "R13")
      (value "4.7K")
      (footprint "eagle-import:R0402")
      (libsource (lib "eagle-import") (part "RES-0402"))
    )
    (comp (ref "R14")
      (value "4.7K")
      (footprint "eagle-import:R0402")
      (libsource (lib "eagle-import") (part "RES-0402"))
    )
    (comp (ref "R16")
      (value "100K")
      (footprint "eagle-import:R0402")
      (libsource (lib "eagle-import") (part "RES-0402"))
    )
    (comp (ref "R17")
      (value "0R")
      (footprint "eagle-import:R0402")
      (libsource (lib "eagle-import") (part "RES-0402"))
    )
    (comp (ref "R18")
      (value "100K")
      (footprint "eagle-import:R0402")
      (libsource (lib "eagle-import") (part "RES-0402"))
    )
    (comp (ref "R19")
      (value "100K")
      (footprint "eagle-import:R0402")
      (libsource (lib "eagle-import") (part "RES-0402"))
    )
    (comp (ref "R20")
      (value "4.7K")
      (footprint "eagle-import:R0402")
      (libsource (lib "eagle-import") (part "RES-0402"))
    )
    (comp (ref "R21")
      (value "0R")
      (footprint "eagle-import:R0402")
      (libsource (lib "eagle-import") (part "RES-0402"))
    )
    (comp (ref "R22")
      (value "10K")
      (footprint "eagle-import:R0402")
      (libsource (lib "eagle-import") (part "RES-0402"))
    )
    (comp (ref "R23")
      (value "100K")
      (footprint "eagle-import:R0402")
      (libsource (lib "eagle-import") (part "RES-0402"))
    )
    (comp (ref "R24")
      (value "100K")
      (footprint "eagle-import:R0402")
      (libsource (lib "eagle-import") (part "RES-0402"))
    )
    (comp (ref "R25")
      (value "1K")
      (footprint "eagle-import:R0402")
      (libsource (lib "eagle-import") (part "RES-0402"))
    )
    (comp (ref "R26")
      (value "10K")
      (footprint "eagle-import:R0402")
      (libsource (lib "eagle-import") (part "RES-0402"))
    )
    (comp (ref "R27")
      (value "10K")
      (footprint "eagle-import:R0402")
      (libsource (lib "eagle-import") (part "RES-0402"))
    )
    (comp (ref "R28")
      (value "1K")
      (footprint "eagle-import:R0402")
      (libsource (lib "eagle-import") (part "RES-0402"))
    )
    (comp (ref "R29")
      (value "100k")
      (footprint "eagle-import:R0402")
      (libsource (lib "eagle-import") (part "RES-0402"))
    )
    (comp (ref "R30")
      (value "330R")
      (footprint "eagle-import:R0402")
      (libsource (lib "eagle-import") (part "RES-0402"))
    )
    (comp (ref "R31")
      (value "1K")
      (footprint "eagle-import:R0402")
      (libsource (lib "eagle-import") (part "RES-0402"))
    )
    (comp (ref "R32")
      (value "DNP")
      (footprint "eagle-import:R0402")
      (libsource (lib "eagle-import") (part "RES-0402"))
    )
    (comp (ref "R33")
      (value "DNP")
      (footprint "eagle-import:R0402")
      (libsource (lib "eagle-import") (part "RES-0402"))
    )
    (comp (ref "R34")
      (value "DNP")
      (footprint "eagle-import:R0402")
      (libsource (lib "eagle-import") (part "RES-0402"))
    )
    (comp (ref "R35")
      (value "33R")
      (footprint "eagle-import:R0402")
      (libsource (lib "eagle-import") (part "RES-0402"))
    )
    (comp (ref "R36")
      (value "100K")
      (footprint "eagle-import:R0402")
      (libsource (lib "eagle-import") (part "RES-0402"))
    )
    (comp (ref "R37")
      (value "100K")
      (footprint "eagle-import:R0402")
      (libsource (lib "eagle-import") (part "RES-0402"))
    )
    (comp (ref "R38")
      (value "4.7K")
      (footprint "eagle-import:R0402")
      (libsource (lib "eagle-import") (part "RES-0402"))
    )
    (comp (ref "R39")
      (value "0R")
      (footprint "eagle-import:R0402")
      (libsource (lib "eagle-import") (part "RES-0402"))
    )
    (comp (ref "R40")
      (value "0R")
      (footprint "eagle-import:R0402")
      (libsource (lib "eagle-import") (part "RES-0402"))
    )
    (comp (ref "R41")
      (value "0R")
      (footprint "eagle-import:R0402")
      (libsource (lib "eagle-import") (part "RES-0402"))
    )
    (comp (ref "R42")
      (value "0R")
      (footprint "eagle-import:R0402")
      (libsource (lib "eagle-import") (part "RES-0402"))
    )
    (comp (ref "R43")
      (value "33R")
      (footprint "eagle-import:R0402")
      (libsource (lib "eagle-import") (part "RES-0402"))
    )
    (comp (ref "R44")
      (value "33R")
      (footprint "eagle-import:R0402")
      (libsource (lib "eagle-import") (part "RES-0402"))
    )
    (comp (ref "R45")
      (value "33R")
      (footprint "eagle-import:R0402")
      (libsource (lib "eagle-import") (part "RES-0402"))
    )
    (comp (ref "R46")
      (value "0R")
      (footprint "eagle-import:R0402")
      (libsource (lib "eagle-import") (part "RES-0402"))
    )
    (comp (ref "R47")
      (value "1k")
      (footprint "eagle-import:R0402")
      (libsource (lib "eagle-import") (part "RES-0402"))
    )
    (comp (ref "R48")
      (value "4.7K")
      (footprint "eagle-import:R0402")
      (libsource (lib "eagle-import") (part "RES-0402"))
    )
    (comp (ref "R49")
      (value "4.7K")
      (footprint "eagle-import:R0402")
      (libsource (lib "eagle-import") (part "RES-0402"))
    )
    (comp (ref "R50")
      (value "DNP")
      (footprint "eagle-import:R0402")
      (libsource (lib "eagle-import") (part "RES-0402"))
    )
    (comp (ref "R51")
      (value "1k")
      (footprint "eagle-import:R0402")
      (libsource (lib "eagle-import") (part "RES-0402"))
    )
    (comp (ref "R52")
      (value "100k")
      (footprint "eagle-import:R0402")
      (libsource (lib "eagle-import") (part "RES-0402"))
    )
    (comp (ref "R53")
      (value "0R")
      (footprint "eagle-import:R0402")
      (libsource (lib "eagle-import") (part "RES-0402"))
    )
    (comp (ref "R54")
      (value "4.7K")
      (footprint "eagle-import:R0402")
      (libsource (lib "eagle-import") (part "RES-0402"))
    )
    (comp (ref "R55")
      (value "22R")
      (footprint "eagle-import:R0402")
      (libsource (lib "eagle-import") (part "RES-0402"))
    )
    (comp (ref "R56")
      (value "22R")
      (footprint "eagle-import:R0402")
      (libsource (lib "eagle-import") (part "RES-0402"))
    )
    (comp (ref "R57")
      (value "33R")
      (footprint "eagle-import:R0402")
      (libsource (lib "eagle-import") (part "RES-0402"))
    )
    (comp (ref "R58")
      (value "DNP")
      (footprint "eagle-import:R0402")
      (libsource (lib "eagle-import") (part "RES-0402"))
    )
    (comp (ref "R59")
      (value "DNP")
      (footprint "eagle-import:R0402")
      (libsource (lib "eagle-import") (part "RES-0402"))
    )
    (comp (ref "R60")
      (value "DNP")
      (footprint "eagle-import:R0402")
      (libsource (lib "eagle-import") (part "RES-0402"))
    )
    (comp (ref "R61")
      (value "4.7K")
      (footprint "eagle-import:R0402")
      (libsource (lib "eagle-import") (part "RES-0402"))
    )
    (comp (ref "R62")
      (value "4.7K")
      (footprint "eagle-import:R0402")
      (libsource (lib "eagle-import") (part "RES-0402"))
    )
    (comp (ref "R63")
      (value "4.7K")
      (footprint "eagle-import:R0402")
      (libsource (lib "eagle-import") (part "RES-0402"))
    )
    (comp (ref "R64")
      (value "DNP")
      (footprint "eagle-import:R0402")
      (libsource (lib "eagle-import") (part "RES-0402"))
    )
    (comp (ref "R65")
      (value "DNP")
      (footprint "eagle-import:R0402")
      (libsource (lib "eagle-import") (part "RES-0402"))
    )
    (comp (ref "R66")
      (value "0R")
      (footprint "eagle-import:R0402")
      (libsource (lib "eagle-import") (part "RES-0402"))
    )
    (comp (ref "R67")
      (value "0R")
      (footprint "eagle-import:R0402")
      (libsource (lib "eagle-import") (part "RES-0402"))
    )
    (comp (ref "R68")
      (value "0R")
      (footprint "eagle-import:R0402")
      (libsource (lib "eagle-import") (part "RES-0402"))
    )
    (comp (ref "R69")
      (value "0R")
      (footprint "eagle-import:R0402")
      (libsource (lib "eagle-import") (part "RES-0402"))
    )
    (comp (ref "R70")
      (value "150K")
      (footprint "eagle-import:R0402")
      (libsource (lib "eagle-import") (part "RES-0402"))
    )
    (comp (ref "R71")
      (value "33K")
      (footprint "eagle-import:R0402")
      (libsource (lib "eagle-import") (part "RES-0402"))
    )
    (comp (ref "R72")
      (value "0R")
      (footprint "eagle-import:R0402")
      (libsource (lib "eagle-import") (part "RES-0402"))
    )
    (comp (ref "R73")
      (value "DNP")
      (footprint "eagle-import:R0402")
      (libsource (lib "eagle-import") (part "RES-0402"))
    )
    (comp (ref "R74")
      (value "33R")
      (footprint "eagle-import:R0402")
      (libsource (lib "eagle-import") (part "RES-0402"))
    )
    (comp (ref "R75")
      (value "33R")
      (footprint "eagle-import:R0402")
      (libsource (lib "eagle-import") (part "RES-0402"))
    )
    (comp (ref "R76")
      (value "33R")
      (footprint "eagle-import:R0402")
      (libsource (lib "eagle-import") (part "RES-0402"))
    )
    (comp (ref "R77")
      (value "10K")
      (footprint "eagle-import:R0402")
      (libsource (lib "eagle-import") (part "RES-0402"))
    )
    (comp (ref "R78")
      (value "100k")
      (footprint "eagle-import:R0402")
      (libsource (lib "eagle-import") (part "RES-0402"))
    )
    (comp (ref "R79")
      (value "0R")
      (footprint "eagle-import:R0402")
      (libsource (lib "eagle-import") (part "RES-0402"))
    )
    (comp (ref "R80")
      (value "100k")
      (footprint "eagle-import:R0402")
      (libsource (lib "eagle-import") (part "RES-0402"))
    )
    (comp (ref "R81")
      (value "0R")
      (footprint "eagle-import:R0402")
      (libsource (lib "eagle-import") (part "RES-0402"))
    )
    (comp (ref "R82")
      (value "0R")
      (footprint "eagle-import:R0402")
      (libsource (lib "eagle-import") (part "RES-0402"))
    )
    (comp (ref "R83")
      (value "0R")
      (footprint "eagle-import:R0402")
      (libsource (lib "eagle-import") (part "RES-0402"))
    )
    (comp (ref "R84")
      (value "100K")
      (footprint "eagle-import:R0402")
      (libsource (lib "eagle-import") (part "RES-0402"))
    )
    (comp (ref "R85")
      (value "100K")
      (footprint "eagle-import:R0402")
      (libsource (lib "eagle-import") (part "RES-0402"))
    )
    (comp (ref "R86")
      (value "100K")
      (footprint "eagle-import:R0402")
      (libsource (lib "eagle-import") (part "RES-0402"))
    )
    (comp (ref "R87")
      (value "100K")
      (footprint "eagle-import:R0402")
      (libsource (lib "eagle-import") (part "RES-0402"))
    )
    (comp (ref "R88")
      (value "1K")
      (footprint "eagle-import:R0402")
      (libsource (lib "eagle-import") (part "RES-0402"))
    )
    (comp (ref "R90")
      (value "DNP")
      (footprint "eagle-import:R0402")
      (libsource (lib "eagle-import") (part "RES-0402"))
    )
    (comp (ref "R91")
      (value "100K")
      (footprint "eagle-import:R0402")
      (libsource (lib "eagle-import") (part "RES-0402"))
    )
    (comp (ref "R93")
      (value "DNP")
      (footprint "eagle-import:R0402")
      (libsource (lib "eagle-import") (part "RES-0402"))
    )
    (comp (ref "R94")
      (value "10K")
      (footprint "eagle-import:R0402")
      (libsource (lib "eagle-import") (part "RES-0402"))
    )
    (comp (ref "R95")
      (value "100K")
      (footprint "eagle-import:R0402")
      (libsource (lib "eagle-import") (part "RES-0402"))
    )
    (comp (ref "R96")
      (value "10K")
      (footprint "eagle-import:R0402")
      (libsource (lib "eagle-import") (part "RES-0402"))
    )
    (comp (ref "R97")
      (value "10K")
      (footprint "eagle-import:R0402")
      (libsource (lib "eagle-import") (part "RES-0402"))
    )
    (comp (ref "R98")
      (value "10K")
      (footprint "eagle-import:R0402")
      (libsource (lib "eagle-import") (part "RES-0402"))
    )
    (comp (ref "R99")
      (value "1K")
      (footprint "eagle-import:R0402")
      (libsource (lib "eagle-import") (part "RES-0402"))
    )
    (comp (ref "R100")
      (value "100K")
      (footprint "eagle-import:R0402")
      (libsource (lib "eagle-import") (part "RES-0402"))
    )
    (comp (ref "R102")
      (value "DNP")
      (footprint "eagle-import:R0402")
      (libsource (lib "eagle-import") (part "RES-0402"))
    )
    (comp (ref "R103")
      (value "DNP")
      (footprint "eagle-import:R0402")
      (libsource (lib "eagle-import") (part "RES-0402"))
    )
    (comp (ref "SW1")
      (value "DHT-1500")
      (footprint "eagle-import:SWITCH-2X3P")
      (libsource (lib "eagle-import") (part "SWITCH-2X3P"))
    )
    (comp (ref "SW3")
      (value "MK-13E03N-G")
      (footprint "eagle-import:SW4-SMD-11.2X3.6MM")
      (libsource (lib "eagle-import") (part "SWITCH-4P"))
    )
    (comp (ref "U1")
      (value "ATSAMD51P19A")
      (footprint "eagle-import:TFBGA120-0.5-8X8MM")
      (libsource (lib "eagle-import") (part "MCU-ATSAMD51P19A"))
    )
    (comp (ref "U2")
      (value "LMV358IDGKR")
      (footprint "eagle-import:MSOP8-0.65-3X3MM")
      (libsource (lib "eagle-import") (part "AMPLIFIER-LMV358-310020007"))
    )
    (comp (ref "U3")
      (value "RPI")
      (footprint "eagle-import:H2X20-SMD-2.54-50.8X5MM-LONG")
      (libsource (lib "eagle-import") (part "RPI-ZERO-LONG"))
    )
    (comp (ref "U4")
      (value "LCD")
      (footprint "eagle-import:LCM18-0.8-60.26X42.72X2.2MM")
      (libsource (lib "eagle-import") (part "LCM-RY24009A0-00"))
    )
    (comp (ref "U5")
      (value "LIS3DHTR")
      (footprint "eagle-import:LGA16-0.5-3X3MM")
      (libsource (lib "eagle-import") (part "SENSOR-MOTION/POSITION-LIS3DHTR-314080105"))
    )
    (comp (ref "U8")
      (value "SENSOR-PD15-22C/TR8")
      (footprint "eagle-import:SNR4-SMD-3.2X2.7MM")
      (libsource (lib "eagle-import") (part "SENSOR-PD15-22C/TR8"))
    )
    (comp (ref "U9")
      (value "SN74LVC1G125DCKR")
      (footprint "eagle-import:SC-70-5")
      (libsource (lib "eagle-import") (part "LOGIC-SN74LVC1G125DCKR-310050019"))
    )
    (comp (ref "U10")
      (value "RTL8720D")
      (footprint "eagle-import:MODULE-32P-0.8-13X12MM-MOTHER")
      (libsource (lib "eagle-import") (part "MODULE-8720DN-MOTHER"))
    )
    (comp (ref "U11")
      (value "ATECC608")
      (footprint "eagle-import:UDFN8-0.5-2X3X0.5MM")
      (libsource (lib "eagle-import") (part "DRIVER-ATECC608A"))
    )
    (comp (ref "U12")
      (value "MP2161GJ")
      (footprint "eagle-import:TSOT23-8")
      (libsource (lib "eagle-import") (part "PMIC-MP2161'GJ'"))
    )
    (comp (ref "U13")
      (value "AP2112K-3.3TRG1")
      (footprint "eagle-import:SOT-23-5")
      (libsource (lib "eagle-import") (part "PMIC-AP2127"))
    )
    (comp (ref "U14")
      (value "W25Q32JVZPIM")
      (footprint "eagle-import:SOIC8-1.27-5.3X5.3MM")
      (libsource (lib "eagle-import") (part "FLASH-W25X80-SS"))
    )
    (comp (ref "USB1")
      (value "USB_TYPE C")
      (footprint "eagle-import:USB2.0-TYPE-C")
      (libsource (lib "eagle-import") (part "USB2.0-TYPE-C"))
    )
    (comp (ref "X2")
      (value "32.768KHz FC-12M")
      (footprint "eagle-import:X2-SMD-L2.0X1.2X0.55MM")
      (libsource (lib "eagle-import") (part "CRYSTAL-2P'NX2012SA'"))
    )
    (comp (ref "X4")
      (value "32MHz / 306010026")
      (footprint "eagle-import:X4-SMD-3.2X2.5X0.7MM")
      (libsource (lib "eagle-import") (part "CRYSTAL-4P-3225"))
    )
  )
  (nets
    (net (code "1") (name "3V3_OUTPUT_CTR") (class "Default")
      (node (ref "R99") (pin "2") (pinfunction "2_2") (pintype "passive"))
      (node (ref "U1") (pin "P12") (pinfunction "PC15/I15/SERCOM7+6.3/TCC0.5+1.1_P12") (pintype "bidirectional"))
    )
    (net (code "2") (name "5V_OUTPUT_CTR") (class "Default")
      (node (ref "R88") (pin "1") (pinfunction "1_1") (pintype "passive"))
      (node (ref "U1") (pin "R11") (pinfunction "PC14/I14/SERCOM7+6.2/TCC0.4+1.0_R11") (pintype "bidirectional"))
    )
    (net (code "3") (name "A0{slash}D0") (class "Default")
      (node (ref "J5") (pin "1") (pinfunction "1_1") (pintype "bidirectional"))
      (node (ref "U1") (pin "J2") (pinfunction "PB08/I8/AIN0.2+1.0/SERCOM4.0/TC4.0/PTC_J2") (pintype "bidirectional"))
      (node (ref "U3") (pin "13") (pinfunction "GPIO27/GEN2_13") (pintype "bidirectional"))
    )
    (net (code "4") (name "A1{slash}D1") (class "Default")
      (node (ref "J5") (pin "2") (pinfunction "2_2") (pintype "bidirectional"))
      (node (ref "U1") (pin "K1") (pinfunction "PB09/I9/AIN0.3+1.1/SERCOM4.1/TC4.0/PTC_K1") (pintype "bidirectional"))
      (node (ref "U3") (pin "15") (pinfunction "GPIO22/GEN3_15") (pintype "bidirectional"))
    )
    (net (code "5") (name "A2{slash}D2") (class "Default")
      (node (ref "U1") (pin "M1") (pinfunction "PA07/I7/AIN0.7/SERCOM0.1/TC1.1/PTC_M1") (pintype "bidirectional"))
      (node (ref "U3") (pin "16") (pinfunction "GEN4/GPIO23_16") (pintype "bidirectional"))
    )
    (net (code "6") (name "A3{slash}D3") (class "Default")
      (node (ref "U1") (pin "F1") (pinfunction "PB04/I4/AIN1.6/PTC_F1") (pintype "bidirectional"))
      (node (ref "U3") (pin "18") (pinfunction "GEN5/GPIO24_18") (pintype "bidirectional"))
    )
    (net (code "7") (name "A4{slash}D4") (class "Default")
      (node (ref "U1") (pin "G1") (pinfunction "PB05/I5/AIN1/7/PTC_G1") (pintype "bidirectional"))
      (node (ref "U3") (pin "22") (pinfunction "GEN6/GPIO25_22") (pintype "bidirectional"))
    )
    (net (code "8") (name "A5{slash}D5") (class "Default")
      (node (ref "U1") (pin "H2") (pinfunction "PB06/I6/AIN1.8/PTC_H2") (pintype "bidirectional"))
      (node (ref "U3") (pin "32") (pinfunction "GPIO12_32") (pintype "bidirectional"))
    )
    (net (code "9") (name "A6{slash}D6") (class "Default")
      (node (ref "U1") (pin "K2") (pinfunction "PA04/I4/VREFB/AIN0.4/SERCOM0.1/TC0.0/PTC_K2") (pintype "bidirectional"))
      (node (ref "U3") (pin "33") (pinfunction "GPIO13_33") (pintype "bidirectional"))
    )
    (net (code "10") (name "A7{slash}D7") (class "Default")
      (node (ref "U1") (pin "J1") (pinfunction "PB07/I7/AIN1.9/PTC_J1") (pintype "bidirectional"))
      (node (ref "U3") (pin "36") (pinfunction "GPIO16_36") (pintype "bidirectional"))
    )
    (net (code "11") (name "A8{slash}D8") (class "Default")
      (node (ref "U1") (pin "L2") (pinfunction "PA06/I6/VREFC/AIN0.6/SERCOM0.1/TC1.0/PTC_L2") (pintype "bidirectional"))
      (node (ref "U3") (pin "37") (pinfunction "GPIO26_37") (pintype "bidirectional"))
    )
    (net (code "12") (name "BUTTON1") (class "Default")
      (node (ref "K1") (pin "2") (pinfunction "2_2") (pintype "bidirectional"))
      (node (ref "R49") (pin "1") (pinfunction "1_1") (pintype "passive"))
      (node (ref "U1") (pin "A10") (pinfunction "PC26/I10/TRACEDATA.1_A10") (pintype "bidirectional"))
    )
    (net (code "13") (name "BUTTON2") (class "Default")
      (node (ref "K2") (pin "2") (pinfunction "2_2") (pintype "bidirectional"))
      (node (ref "R3") (pin "1") (pinfunction "1_1") (pintype "passive"))
      (node (ref "U1") (pin "A9") (pinfunction "PC27/I11/SERCOM1.0/TRACECLK_A9") (pintype "bidirectional"))
    )
    (net (code "14") (name "BUTTON3") (class "Default")
      (node (ref "K3") (pin "2") (pinfunction "2_2") (pintype "bidirectional"))
      (node (ref "R4") (pin "1") (pinfunction "1_1") (pintype "passive"))
      (node (ref "U1") (pin "B9") (pinfunction "PC28/I12/SERCOM1.1/TRACEDATA.0_B9") (pintype "bidirectional"))
    )
    (net (code "15") (name "BUZZER_CTR") (class "Default")
      (node (ref "R5") (pin "1") (pinfunction "1_1") (pintype "passive"))
      (node (ref "U1") (pin "P9") (pinfunction "PD11/I6/SERCOM7+6.3/TCC0.4_P9") (pintype "bidirectional"))
    )
    (net (code "16") (name "DAC0") (class "Default")
      (node (ref "U1") (pin "E1") (pinfunction "PA02/I2/AIN0.0/VOUT0_E1") (pintype "bidirectional"))
      (node (ref "U3") (pin "11") (pinfunction "GPIO17/GEN0_11") (pintype "bidirectional"))
    )
    (net (code "17") (name "DAC1") (class "Default")
      (node (ref "U1") (pin "L1") (pinfunction "PA05/I5/AIN0.5/VOUT1/SERCOM0.2/TC0.1_L1") (pintype "bidirectional"))
      (node (ref "U3") (pin "26") (pinfunction "~{CE}/GPIO7_26") (pintype "bidirectional"))
    )
    (net (code "18") (name "DN") (class "Default")
      (node (ref "D3") (pin "1") (pinfunction "1_1") (pintype "bidirectional"))
      (node (ref "R55") (pin "1") (pinfunction "1_1") (pintype "passive"))
      (node (ref "USB1") (pin "A7") (pinfunction "A7/DN1_A7") (pintype "bidirectional"))
      (node (ref "USB1") (pin "B7") (pinfunction "B7/DN2_B7") (pintype "bidirectional"))
    )
    (net (code "19") (name "DP") (class "Default")
      (node (ref "D4") (pin "1") (pinfunction "1_1") (pintype "bidirectional"))
      (node (ref "R56") (pin "2") (pinfunction "2_2") (pintype "passive"))
      (node (ref "USB1") (pin "A6") (pinfunction "A6/DP1_A6") (pintype "bidirectional"))
      (node (ref "USB1") (pin "B6") (pinfunction "B6/DP2_B6") (pintype "bidirectional"))
    )
    (net (code "20") (name "FPC_D3{slash}PWM3") (class "Default")
      (node (ref "J6") (pin "4") (pinfunction "4_4") (pintype "bidirectional"))
      (node (ref "U1") (pin "A12") (pinfunction "PB28/I14/SEROM2+4.2/TCC1.4/I2SSCK.1_A12") (pintype "bidirectional"))
    )
    (net (code "21") (name "FPC_D4{slash}PWM4") (class "Default")
      (node (ref "J6") (pin "5") (pinfunction "5_5") (pintype "bidirectional"))
      (node (ref "U1") (pin "G15") (pinfunction "PB17/SERCOM5.1/I2SMCK0/TC6.1+TCC3.1+0.5_G15") (pintype "bidirectional"))
    )
    (net (code "22") (name "FPC_D5{slash}PWM5") (class "Default")
      (node (ref "J6") (pin "6") (pinfunction "6_6") (pintype "bidirectional"))
      (node (ref "U1") (pin "B11") (pinfunction "PB29/I15/SERCOM2+4.3/TCC1.5/I2SMCK.1_B11") (pintype "bidirectional"))
    )
    (net (code "23") (name "FPC_D6{slash}PWM6") (class "Default")
      (node (ref "J6") (pin "7") (pinfunction "7_7") (pintype "bidirectional"))
      (node (ref "U1") (pin "R13") (pinfunction "PA14/I14/SERCOM2+4.2/TC3.0+TCC2.0+1.2_R13") (pintype "bidirectional"))
    )
    (net (code "24") (name "FPC_D7{slash}A7") (class "Default")
      (node (ref "J6") (pin "8") (pinfunction "8_8") (pintype "bidirectional"))
      (node (ref "U1") (pin "C2") (pinfunction "PC01/I1/ADC1.11_C2") (pintype "bidirectional"))
    )
    (net (code "25") (name "FPC_D8{slash}A8") (class "Default")
      (node (ref "J6") (pin "9") (pinfunction "9_9") (pintype "bidirectional"))
      (node (ref "U1") (pin "D1") (pinfunction "PC02/I2/ADC1.4_D1") (pintype "bidirectional"))
    )
    (net (code "26") (name "FPC_D9{slash}A9") (class "Default")
      (node (ref "J6") (pin "10") (pinfunction "10_10") (pintype "bidirectional"))
      (node (ref "U1") (pin "E2") (pinfunction "PC03/I3/ADC1.5_E2") (pintype "bidirectional"))
    )
    (net (code "27") (name "FPC_D10{slash}PWM10") (class "Default")
      (node (ref "J6") (pin "11") (pinfunction "11_11") (pintype "bidirectional"))
      (node (ref "U1") (pin "N1") (pinfunction "PC04/I4/SERCOM6.0/TCC0.0_N1") (pintype "bidirectional"))
    )
    (net (code "28") (name "FPC_D11{slash}A11") (class "Default")
      (node (ref "J6") (pin "12") (pinfunction "12_12") (pintype "bidirectional"))
      (node (ref "U1") (pin "B4") (pinfunction "PC31/I15/AIN1.13_B4") (pintype "bidirectional"))
    )
    (net (code "29") (name "FPC_D12{slash}A12") (class "Default")
      (node (ref "J6") (pin "13") (pinfunction "13_13") (pintype "bidirectional"))
      (node (ref "U1") (pin "G2") (pinfunction "PD00/I0/AIN1.14_G2") (pintype "bidirectional"))
    )
    (net (code "30") (name "FPC_D13{slash}A13") (class "Default")
      (node (ref "R79") (pin "2") (pinfunction "2_2") (pintype "passive"))
      (node (ref "U1") (pin "H1") (pinfunction "PD01/I1/AIN1.14_H1") (pintype "bidirectional"))
    )
    (net (code "31") (name "GND_POWER") (class "Default")
      (node (ref "ANT2") (pin "1") (pinfunction "1_1") (pintype "bidirectional"))
      (node (ref "C1") (pin "1") (pinfunction "1_1") (pintype "passive"))
      (node (ref "C10") (pin "2") (pinfunction "2_2") (pintype "passive"))
      (node (ref "C11") (pin "1") (pinfunction "1_1") (pintype "passive"))
      (node (ref "C12") (pin "2") (pinfunction "2_2") (pintype "passive"))
      (node (ref "C13") (pin "2") (pinfunction "2_2") (pintype "passive"))
      (node (ref "C14") (pin "1") (pinfunction "1_1") (pintype "passive"))
      (node (ref "C15") (pin "2") (pinfunction "2_2") (pintype "passive"))
      (node (ref "C16") (pin "2") (pinfunction "2_2") (pintype "passive"))
      (node (ref "C2") (pin "1") (pinfunction "1_1") (pintype "passive"))
      (node (ref "C27") (pin "1") (pinfunction "1_1") (pintype "passive"))
      (node (ref "C28") (pin "1") (pinfunction "1_1") (pintype "passive"))
      (node (ref "C29") (pin "1") (pinfunction "1_1") (pintype "passive"))
      (node (ref "C3") (pin "1") (pinfunction "1_1") (pintype "passive"))
      (node (ref "C30") (pin "1") (pinfunction "1_1") (pintype "passive"))
      (node (ref "C31") (pin "1") (pinfunction "1_1") (pintype "passive"))
      (node (ref "C32") (pin "2") (pinfunction "2_2") (pintype "passive"))
      (node (ref "C33") (pin "2") (pinfunction "2_2") (pintype "passive"))
      (node (ref "C35") (pin "2") (pinfunction "2_2") (pintype "passive"))
      (node (ref "C36") (pin "2") (pinfunction "2_2") (pintype "passive"))
      (node (ref "C37") (pin "2") (pinfunction "2_2") (pintype "passive"))
      (node (ref "C38") (pin "2") (pinfunction "2_2") (pintype "passive"))
      (node (ref "C39") (pin "2") (pinfunction "2_2") (pintype "passive"))
      (node (ref "C4") (pin "1") (pinfunction "1_1") (pintype "passive"))
      (node (ref "C40") (pin "2") (pinfunction "2_2") (pintype "passive"))
      (node (ref "C41") (pin "2") (pinfunction "2_2") (pintype "passive"))
      (node (ref "C42") (pin "2") (pinfunction "2_2") (pintype "passive"))
      (node (ref "C43") (pin "2") (pinfunction "2_2") (pintype "passive"))
      (node (ref "C48") (pin "2") (pinfunction "2_2") (pintype "passive"))
      (node (ref "C49") (pin "1") (pinfunction "1_1") (pintype "passive"))
      (node (ref "C5") (pin "1") (pinfunction "1_1") (pintype "passive"))
      (node (ref "C50") (pin "1") (pinfunction "1_1") (pintype "passive"))
      (node (ref "C51") (pin "2") (pinfunction "2_2") (pintype "passive"))
      (node (ref "C52") (pin "2") (pinfunction "2_2") (pintype "passive"))
      (node (ref "C53") (pin "2") (pinfunction "2_2") (pintype "passive"))
      (node (ref "C54") (pin "2") (pinfunction "2_2") (pintype "passive"))
      (node (ref "C6") (pin "1") (pinfunction "1_1") (pintype "passive"))
      (node (ref "C60") (pin "2") (pinfunction "2_2") (pintype "passive"))
      (node (ref "C61") (pin "2") (pinfunction "2_2") (pintype "passive"))
      (node (ref "C62") (pin "2") (pinfunction "2_2") (pintype "passive"))
      (node (ref "C63") (pin "-") (pinfunction "-_-") (pintype "passive"))
      (node (ref "C64") (pin "1") (pinfunction "1_1") (pintype "passive"))
      (node (ref "C65") (pin "1") (pinfunction "1_1") (pintype "passive"))
      (node (ref "C66") (pin "1") (pinfunction "1_1") (pintype "passive"))
      (node (ref "C67") (pin "1") (pinfunction "1_1") (pintype "passive"))
      (node (ref "C7") (pin "2") (pinfunction "2_2") (pintype "passive"))
      (node (ref "C8") (pin "2") (pinfunction "2_2") (pintype "passive"))
      (node (ref "C9") (pin "2") (pinfunction "2_2") (pintype "passive"))
      (node (ref "D1") (pin "1") (pinfunction "1_1") (pintype "bidirectional"))
      (node (ref "D15") (pin "10") (pinfunction "10_10") (pintype "bidirectional"))
      (node (ref "D15") (pin "5") (pinfunction "10_5") (pintype "bidirectional"))
      (node (ref "D2") (pin "2") (pinfunction "2_2") (pintype "bidirectional"))
      (node (ref "D3") (pin "2") (pinfunction "2_2") (pintype "bidirectional"))
      (node (ref "D4") (pin "2") (pinfunction "2_2") (pintype "bidirectional"))
      (node (ref "D6") (pin "1") (pinfunction "1_1") (pintype "bidirectional"))
      (node (ref "D8") (pin "1") (pinfunction "1_1") (pintype "bidirectional"))
      (node (ref "J1") (pin "6") (pinfunction "VSS_6") (pintype "bidirectional"))
      (node (ref "J1") (pin "G1") (pinfunction "G1_G1") (pintype "bidirectional"))
      (node (ref "J1") (pin "G2") (pinfunction "G2_G2") (pintype "bidirectional"))
      (node (ref "J1") (pin "G3") (pinfunction "G3_G3") (pintype "bidirectional"))
      (node (ref "J1") (pin "G4") (pinfunction "G3_G4") (pintype "bidirectional"))
      (node (ref "J2") (pin "2") (pinfunction "2_2") (pintype "bidirectional"))
      (node (ref "J3") (pin "6") (pinfunction "6_6") (pintype "bidirectional"))
      (node (ref "J3") (pin "P1") (pinfunction "P1_P1") (pintype "bidirectional"))
      (node (ref "J3") (pin "P2") (pinfunction "P2_P2") (pintype "bidirectional"))
      (node (ref "J4") (pin "4") (pinfunction "4_4") (pintype "bidirectional"))
      (node (ref "J5") (pin "4") (pinfunction "4_4") (pintype "bidirectional"))
      (node (ref "J6") (pin "17") (pinfunction "17_17") (pintype "bidirectional"))
      (node (ref "J6") (pin "18") (pinfunction "18_18") (pintype "bidirectional"))
      (node (ref "J6") (pin "P1") (pinfunction "P1_P1") (pintype "bidirectional"))
      (node (ref "J6") (pin "P2") (pinfunction "P2_P2") (pintype "bidirectional"))
      (node (ref "J7") (pin "5") (pinfunction "5_5") (pintype "bidirectional"))
      (node (ref "K1") (pin "1") (pinfunction "1_1") (pintype "bidirectional"))
      (node (ref "K1") (pin "3") (pinfunction "S1_3") (pintype "bidirectional"))
      (node (ref "K1") (pin "4") (pinfunction "S2_4") (pintype "bidirectional"))
      (node (ref "K2") (pin "1") (pinfunction "1_1") (pintype "bidirectional"))
      (node (ref "K2") (pin "3") (pinfunction "S1_3") (pintype "bidirectional"))
      (node (ref "K2") (pin "4") (pinfunction "S2_4") (pintype "bidirectional"))
      (node (ref "K3") (pin "1") (pinfunction "1_1") (pintype "bidirectional"))
      (node (ref "K3") (pin "3") (pinfunction "S1_3") (pintype "bidirectional"))
      (node (ref "K3") (pin "4") (pinfunction "S2_4") (pintype "bidirectional"))
      (node (ref "LED1") (pin "2") (pinfunction "-_2") (pintype "passive"))
      (node (ref "MIC1") (pin "2") (pinfunction "-_2") (pintype "bidirectional"))
      (node (ref "MIC1") (pin "3") (pinfunction "-_3") (pintype "bidirectional"))
      (node (ref "MIC1") (pin "4") (pinfunction "-_4") (pintype "bidirectional"))
      (node (ref "MIC1") (pin "5") (pinfunction "-_5") (pintype "bidirectional"))
      (node (ref "Q1") (pin "2") (pinfunction "S_2") (pintype "passive"))
      (node (ref "Q13") (pin "2") (pinfunction "S_2") (pintype "passive"))
      (node (ref "Q16") (pin "2") (pinfunction "S_2") (pintype "passive"))
      (node (ref "Q3") (pin "2") (pinfunction "S_2") (pintype "passive"))
      (node (ref "Q4") (pin "2") (pinfunction "S_2") (pintype "passive"))
      (node (ref "R1") (pin "1") (pinfunction "1_1") (pintype "passive"))
      (node (ref "R100") (pin "1") (pinfunction "1_1") (pintype "passive"))
      (node (ref "R16") (pin "2") (pinfunction "2_2") (pintype "passive"))
      (node (ref "R19") (pin "2") (pinfunction "2_2") (pintype "passive"))
      (node (ref "R2") (pin "1") (pinfunction "1_1") (pintype "passive"))
      (node (ref "R23") (pin "2") (pinfunction "2_2") (pintype "passive"))
      (node (ref "R25") (pin "1") (pinfunction "1_1") (pintype "passive"))
      (node (ref "R28") (pin "1") (pinfunction "1_1") (pintype "passive"))
      (node (ref "R50") (pin "2") (pinfunction "2_2") (pintype "passive"))
      (node (ref "R52") (pin "1") (pinfunction "1_1") (pintype "passive"))
      (node (ref "R54") (pin "2") (pinfunction "2_2") (pintype "passive"))
      (node (ref "R7") (pin "1") (pinfunction "1_1") (pintype "passive"))
      (node (ref "R72") (pin "1") (pinfunction "1_1") (pintype "passive"))
      (node (ref "R77") (pin "1") (pinfunction "1_1") (pintype "passive"))
      (node (ref "R78") (pin "1") (pinfunction "1_1") (pintype "passive"))
      (node (ref "R80") (pin "2") (pinfunction "2_2") (pintype "passive"))
      (node (ref "R91") (pin "2") (pinfunction "2_2") (pintype "passive"))
      (node (ref "R93") (pin "1") (pinfunction "1_1") (pintype "passive"))
      (node (ref "R95") (pin "1") (pinfunction "1_1") (pintype "passive"))
      (node (ref "R97") (pin "1") (pinfunction "1_1") (pintype "passive"))
      (node (ref "R98") (pin "1") (pinfunction "1_1") (pintype "passive"))
      (node (ref "SW1") (pin "5") (pinfunction "5_5") (pintype "bidirectional"))
      (node (ref "SW1") (pin "7") (pinfunction "7_7") (pintype "bidirectional"))
      (node (ref "SW1") (pin "8") (pinfunction "8_8") (pintype "bidirectional"))
      (node (ref "SW3") (pin "3") (pinfunction "P$3_3") (pintype "bidirectional"))
      (node (ref "U1") (pin "D2") (pinfunction "GNDIO0_D2") (pintype "bidirectional"))
      (node (ref "U1") (pin "F6") (pinfunction "GNDIO7_F6") (pintype "bidirectional"))
      (node (ref "U1") (pin "F9") (pinfunction "GNDIO6_F9") (pintype "bidirectional"))
      (node (ref "U1") (pin "G10") (pinfunction "GNDIO5_G10") (pintype "bidirectional"))
      (node (ref "U1") (pin "H6") (pinfunction "GNDANA0_H6") (pintype "bidirectional"))
      (node (ref "U1") (pin "J10") (pinfunction "GNDIO4_J10") (pintype "bidirectional"))
      (node (ref "U1") (pin "J6") (pinfunction "GNDIO1_J6") (pintype "bidirectional"))
      (node (ref "U1") (pin "K8") (pinfunction "GNDIO2_K8") (pintype "bidirectional"))
      (node (ref "U1") (pin "K9") (pinfunction "GNDIO3_K9") (pintype "bidirectional"))
      (node (ref "U10") (pin "1") (pinfunction "1_1") (pintype "bidirectional"))
      (node (ref "U10") (pin "15") (pinfunction "15_15") (pintype "bidirectional"))
      (node (ref "U10") (pin "21") (pinfunction "21_21") (pintype "bidirectional"))
      (node (ref "U10") (pin "30") (pinfunction "30_30") (pintype "bidirectional"))
      (node (ref "U10") (pin "32") (pinfunction "32_32") (pintype "bidirectional"))
      (node (ref "U10") (pin "51") (pinfunction "PAD_51") (pintype "bidirectional"))
      (node (ref "U10") (pin "54") (pinfunction "PAD_54") (pintype "bidirectional"))
      (node (ref "U10") (pin "60") (pinfunction "PAD_60") (pintype "bidirectional"))
      (node (ref "U10") (pin "61") (pinfunction "PAD_61") (pintype "bidirectional"))
      (node (ref "U11") (pin "4") (pinfunction "GND_4") (pintype "bidirectional"))
      (node (ref "U11") (pin "9") (pinfunction "PAD_9") (pintype "bidirectional"))
      (node (ref "U12") (pin "4") (pinfunction "PGND_4") (pintype "bidirectional"))
      (node (ref "U12") (pin "6") (pinfunction "AGND_6") (pintype "bidirectional"))
      (node (ref "U13") (pin "2") (pinfunction "GND_2") (pintype "bidirectional"))
      (node (ref "U14") (pin "4") (pinfunction "GND_4") (pintype "bidirectional"))
      (node (ref "U2") (pin "4") (pinfunction "GND_4") (pintype "power_in"))
      (node (ref "U3") (pin "14") (pinfunction "GND_14") (pintype "power_in"))
      (node (ref "U3") (pin "20") (pinfunction "GND_20") (pintype "power_in"))
      (node (ref "U3") (pin "25") (pinfunction "GND_25") (pintype "power_in"))
      (node (ref "U3") (pin "30") (pinfunction "GND_30") (pintype "power_in"))
      (node (ref "U3") (pin "34") (pinfunction "GND_34") (pintype "power_in"))
      (node (ref "U3") (pin "39") (pinfunction "GND_39") (pintype "power_in"))
      (node (ref "U3") (pin "6") (pinfunction "GND_6") (pintype "power_in"))
      (node (ref "U3") (pin "9") (pinfunction "GND_9") (pintype "power_in"))
      (node (ref "U4") (pin "1") (pinfunction "GND_1") (pintype "bidirectional"))
      (node (ref "U4") (pin "8") (pinfunction "GND_8") (pintype "bidirectional"))
      (node (ref "U5") (pin "10") (pinfunction "RES_10") (pintype "bidirectional"))
      (node (ref "U5") (pin "12") (pinfunction "GND_12") (pintype "bidirectional"))
      (node (ref "U5") (pin "5") (pinfunction "GND_5") (pintype "bidirectional"))
      (node (ref "U5") (pin "7") (pinfunction "SDO/SA0_7") (pintype "bidirectional"))
      (node (ref "U9") (pin "3") (pinfunction "GND_3") (pintype "bidirectional"))
      (node (ref "USB1") (pin "A1_B12") (pinfunction "A1/B12/GND_A1_B12") (pintype "bidirectional"))
      (node (ref "USB1") (pin "B1_A12") (pinfunction "B1/A12/GND_B1_A12") (pintype "bidirectional"))
      (node (ref "USB1") (pin "S1") (pinfunction "S1_S1") (pintype "bidirectional"))
      (node (ref "USB1") (pin "S2") (pinfunction "S2_S2") (pintype "bidirectional"))
      (node (ref "USB1") (pin "S3") (pinfunction "S3_S3") (pintype "bidirectional"))
      (node (ref "USB1") (pin "S4") (pinfunction "S4_S4") (pintype "bidirectional"))
      (node (ref "USB1") (pin "S5") (pinfunction "S1_S5") (pintype "bidirectional"))
      (node (ref "USB1") (pin "S6") (pinfunction "S2_S6") (pintype "bidirectional"))
      (node (ref "X4") (pin "2") (pinfunction "GND_2") (pintype "bidirectional"))
      (node (ref "X4") (pin "4") (pinfunction "GND_4") (pintype "bidirectional"))
    )
    (net (code "32") (name "GPCLK0") (class "Default")
      (node (ref "U1") (pin "R5") (pinfunction "PB14/I14/SERCOM4.2/PCC8/TC5.0+TCC4.0+0.2/PTC_R5") (pintype "bidirectional"))
      (node (ref "U3") (pin "7") (pinfunction "GPIO4/GCKL_7") (pintype "bidirectional"))
    )
    (net (code "33") (name "GPCLK1") (class "Default")
      (node (ref "U1") (pin "R4") (pinfunction "PB12/I12/SERCOM4.0/I2SCK1/TC4.0+TCC3.0+0.1/PTC_R4") (pintype "bidirectional"))
      (node (ref "U3") (pin "29") (pinfunction "GPIO5_29") (pintype "bidirectional"))
    )
    (net (code "34") (name "GPCLK2") (class "Default")
      (node (ref "U1") (pin "P6") (pinfunction "PB13/I13/SERCOM4.1/I2SMCK1/TC4.1+TCC3.1+0.1/PTC_P6") (pintype "bidirectional"))
      (node (ref "U3") (pin "31") (pinfunction "GPIO6_31") (pintype "bidirectional"))
    )
    (net (code "35") (name "GYROSCOPE_INT1") (class "Default")
      (node (ref "U1") (pin "K14") (pinfunction "PC21/I5/TCC0.5/SDHC1.SDWP_K14") (pintype "bidirectional"))
      (node (ref "U5") (pin "11") (pinfunction "INT1_11") (pintype "bidirectional"))
    )
    (net (code "36") (name "I2C0_SCL") (class "Default")
      (node (ref "R13") (pin "2") (pinfunction "2_2") (pintype "passive"))
      (node (ref "U1") (pin "R12") (pinfunction "PA12/I12/I2C/SERCOM2.0+4.1/TC2.0+TCC0.7+1.3_R12") (pintype "bidirectional"))
      (node (ref "U11") (pin "6") (pinfunction "SCL_6") (pintype "bidirectional"))
      (node (ref "U3") (pin "28") (pinfunction "ID_SC_28") (pintype "bidirectional"))
      (node (ref "U5") (pin "4") (pinfunction "SCL/SPC_4") (pintype "bidirectional"))
    )
    (net (code "37") (name "I2C0_SDA") (class "Default")
      (node (ref "R14") (pin "2") (pinfunction "2_2") (pintype "passive"))
      (node (ref "U1") (pin "P13") (pinfunction "PA13/I13/I2C/SERCOM2.1+4.0/TC2.1+TCC0.7+1.3_P13") (pintype "bidirectional"))
      (node (ref "U11") (pin "5") (pinfunction "SDA_5") (pintype "bidirectional"))
      (node (ref "U3") (pin "27") (pinfunction "ID_SD_27") (pintype "bidirectional"))
      (node (ref "U5") (pin "6") (pinfunction "SDA/SDI/SDO_6") (pintype "bidirectional"))
    )
    (net (code "38") (name "I2C1_SCL") (class "Default")
      (node (ref "J4") (pin "1") (pinfunction "1_1") (pintype "bidirectional"))
      (node (ref "R33") (pin "1") (pinfunction "1_1") (pintype "passive"))
      (node (ref "U1") (pin "R15") (pinfunction "PA16/I2C/I0/SERCOM1.0+3.1/TC2.0+TCC1.0+0.4/PTC_R15") (pintype "bidirectional"))
      (node (ref "U3") (pin "5") (pinfunction "GPIO3/SCL1_5") (pintype "bidirectional"))
    )
    (net (code "39") (name "I2C1_SDA") (class "Default")
      (node (ref "J4") (pin "2") (pinfunction "2_2") (pintype "bidirectional"))
      (node (ref "R34") (pin "1") (pinfunction "1_1") (pintype "passive"))
      (node (ref "U1") (pin "P14") (pinfunction "PA17/I2C/I1/SERCOM1.1+3.0/TC2.1+TCC1.1+0.5/PTC_P14") (pintype "bidirectional"))
      (node (ref "U3") (pin "3") (pinfunction "GPIO2/SDA1_3") (pintype "bidirectional"))
    )
    (net (code "40") (name "I2S_BLCK") (class "Default")
      (node (ref "U1") (pin "H15") (pinfunction "PB16/I0/SERCOM5.0/I2SCK0/TC6.0+TCC3.0+0.4_H15") (pintype "bidirectional"))
      (node (ref "U3") (pin "12") (pinfunction "GPIO18_12") (pintype "bidirectional"))
    )
    (net (code "41") (name "I2S_LRCLK") (class "Default")
      (node (ref "U1") (pin "E14") (pinfunction "PA20/I4/SERCOM3+5.2/I2SFS0/TC7.0+TCC1.4+0.0/PTC_E14") (pintype "bidirectional"))
      (node (ref "U3") (pin "35") (pinfunction "GPIO19_35") (pintype "bidirectional"))
    )
    (net (code "42") (name "I2S_SDIN") (class "Default")
      (node (ref "U1") (pin "D15") (pinfunction "PA21/I5/SERCOM3+5.3/I2SDO/TC7.1+TCC1.5+0.1/PTC_D15") (pintype "bidirectional"))
      (node (ref "U3") (pin "38") (pinfunction "GPIO20_38") (pintype "bidirectional"))
    )
    (net (code "43") (name "I2S_SDOUT") (class "Default")
      (node (ref "U1") (pin "D14") (pinfunction "PA22/I2C/16/SERCOM3.0+5.1/I2SDI/TC4.0+TCC1.6+0.2/PTC_D14") (pintype "bidirectional"))
      (node (ref "U3") (pin "40") (pinfunction "GPIO21_40") (pintype "bidirectional"))
    )
    (net (code "44") (name "IRQ0") (class "Default")
      (node (ref "R103") (pin "1") (pinfunction "1_1") (pintype "passive"))
      (node (ref "U1") (pin "L15") (pinfunction "PC20/I4/TCC0.4/SDHC1.SDCD_L15") (pintype "bidirectional"))
      (node (ref "U10") (pin "2") (pinfunction "2_2") (pintype "bidirectional"))
    )
    (net (code "45") (name "IR_CTL") (class "Default")
      (node (ref "R47") (pin "2") (pinfunction "2_2") (pintype "passive"))
      (node (ref "U1") (pin "B5") (pinfunction "PB31/I15/SERCOM5.0/TC0.1+TCC4.1+0.7_B5") (pintype "bidirectional"))
    )
    (net (code "46") (name "LCDVCC_3V3") (class "Default")
      (node (ref "C29") (pin "2") (pinfunction "2_2") (pintype "passive"))
      (node (ref "C30") (pin "2") (pinfunction "2_2") (pintype "passive"))
      (node (ref "C31") (pin "2") (pinfunction "2_2") (pintype "passive"))
      (node (ref "FB2") (pin "2") (pinfunction "2_2") (pintype "bidirectional"))
      (node (ref "R48") (pin "2") (pinfunction "2_2") (pintype "passive"))
      (node (ref "U4") (pin "10") (pinfunction "LEDA_10") (pintype "bidirectional"))
      (node (ref "U4") (pin "9") (pinfunction "VCC_9") (pintype "bidirectional"))
    )
    (net (code "47") (name "LCD_BACKLIGHT_CTR") (class "Default")
      (node (ref "R17") (pin "2") (pinfunction "2_2") (pintype "passive"))
      (node (ref "U1") (pin "N2") (pinfunction "PC05/I5/SERCOM6.0_N2") (pintype "bidirectional"))
    )
    (net (code "48") (name "LCD_CS") (class "Default")
      (node (ref "R74") (pin "2") (pinfunction "2_2") (pintype "passive"))
      (node (ref "U1") (pin "E15") (pinfunction "PB21/SERCOM3.1+7.0/TCC1.3_E15") (pintype "bidirectional"))
    )
    (net (code "49") (name "LCD_D{slash}C") (class "Default")
      (node (ref "R57") (pin "2") (pinfunction "2_2") (pintype "passive"))
      (node (ref "U1") (pin "P1") (pinfunction "PC06/I6/SERCOM6.2/SDHC0.SDCD_P1") (pintype "bidirectional"))
    )
    (net (code "50") (name "LCD_MISO") (class "Default")
      (node (ref "R76") (pin "2") (pinfunction "2_2") (pintype "passive"))
      (node (ref "U1") (pin "G14") (pinfunction "PB18/I2/SERCOM5+7.2/TCC1.0+QDI.0_G14") (pintype "bidirectional"))
    )
    (net (code "51") (name "LCD_MOSI") (class "Default")
      (node (ref "R75") (pin "2") (pinfunction "2_2") (pintype "passive"))
      (node (ref "U1") (pin "F15") (pinfunction "PB19/I3/SERCOM5+7.3/CC1.1/QDI.1_F15") (pintype "bidirectional"))
    )
    (net (code "52") (name "LCD_RESET") (class "Default")
      (node (ref "R48") (pin "1") (pinfunction "1_1") (pintype "passive"))
      (node (ref "U1") (pin "P2") (pinfunction "PC07/I9/SERCOM6.3/SDHC0.SDWP_P2") (pintype "bidirectional"))
      (node (ref "U4") (pin "2") (pinfunction "RESET_2") (pintype "bidirectional"))
    )
    (net (code "53") (name "LCD_SCK") (class "Default")
      (node (ref "R35") (pin "2") (pinfunction "2_2") (pintype "passive"))
      (node (ref "U1") (pin "F14") (pinfunction "PB20/I4/SERCOM3.0+7.1/TCC1.2/QDI.2_F14") (pintype "bidirectional"))
    )
    (net (code "54") (name "LCD_XL") (class "Default")
      (node (ref "R39") (pin "1") (pinfunction "1_1") (pintype "passive"))
      (node (ref "U1") (pin "P10") (pinfunction "PC10/I10/SERCOM6.2+7.2/TCC0.0+1.4_P10") (pintype "bidirectional"))
    )
    (net (code "55") (name "LCD_XR") (class "Default")
      (node (ref "R41") (pin "1") (pinfunction "1_1") (pintype "passive"))
      (node (ref "U1") (pin "R10") (pinfunction "PC12/I12/SERCOM7.0+6.1/TCC0.2+1.6_R10") (pintype "bidirectional"))
    )
    (net (code "56") (name "LCD_YD") (class "Default")
      (node (ref "R42") (pin "1") (pinfunction "1_1") (pintype "passive"))
      (node (ref "U1") (pin "P11") (pinfunction "PC13/I13/SERCOM7.1+6.0/TCC0.3+1.7_P11") (pintype "bidirectional"))
    )
    (net (code "57") (name "LCD_YU") (class "Default")
      (node (ref "R40") (pin "1") (pinfunction "1_1") (pintype "passive"))
      (node (ref "U1") (pin "R9") (pinfunction "PC11/I11/SERCOM6+7.3/TCC0.1+1.5_R9") (pintype "bidirectional"))
    )
    (net (code "58") (name "MCU_FLASH_QSPI_CLK") (class "Default")
      (node (ref "U1") (pin "R3") (pinfunction "PB10/I10/SERCOM4.2/I2SDI/TC5.0+TCC0.4+1.0_R3") (pintype "bidirectional"))
      (node (ref "U14") (pin "6") (pinfunction "CLK_6") (pintype "bidirectional"))
    )
    (net (code "59") (name "MCU_FLASH_QSPI_CS") (class "Default")
      (node (ref "R32") (pin "1") (pinfunction "1_1") (pintype "passive"))
      (node (ref "U1") (pin "P5") (pinfunction "PB11/I11/SERCOM4.3/I2SFS1/TC5.1+TCC0.5+1.1_P5") (pintype "bidirectional"))
      (node (ref "U14") (pin "1") (pinfunction "/CS_1") (pintype "bidirectional"))
    )
    (net (code "60") (name "MCU_FLASH_QSPI_IO0") (class "Default")
      (node (ref "U1") (pin "R1") (pinfunction "PA08/I2C/AIN0.8+1.2/SERCOM0.0+2.1/I2SMCK1/TC0.0+TCC0.0+1.4/PTC_R1") (pintype "bidirectional"))
      (node (ref "U14") (pin "5") (pinfunction "DIO_5") (pintype "bidirectional"))
    )
    (net (code "61") (name "MCU_FLASH_QSPI_IO1") (class "Default")
      (node (ref "U1") (pin "P3") (pinfunction "PA09/I2C/I9/AIN0.9+1.3/SERCOM0.1+2.0/I2SFS0/TC0.1+TCC0.1+1.5/PTC_P3") (pintype "bidirectional"))
      (node (ref "U14") (pin "2") (pinfunction "DO_2") (pintype "bidirectional"))
    )
    (net (code "62") (name "MCU_FLASH_QSPI_IO2") (class "Default")
      (node (ref "R58") (pin "1") (pinfunction "1_1") (pintype "passive"))
      (node (ref "U1") (pin "R2") (pinfunction "PA10/I10/AIN0.10/SERCOM0+2.2/I2SCK1/TC1.0+TCC0.2+1.6/PTC_R2") (pintype "bidirectional"))
      (node (ref "U14") (pin "3") (pinfunction "/WP_3") (pintype "bidirectional"))
    )
    (net (code "63") (name "MCU_FLASH_QSPI_IO3") (class "Default")
      (node (ref "R59") (pin "1") (pinfunction "1_1") (pintype "passive"))
      (node (ref "U1") (pin "P4") (pinfunction "PA11/I11/AIN0.11/SERCOM0+2.3/I2SDO/TC1.1+TCC0.3+1.7_P4") (pintype "bidirectional"))
      (node (ref "U14") (pin "7") (pinfunction "/HOLD_7") (pintype "bidirectional"))
    )
    (net (code "64") (name "MCU_RESET") (class "Default")
      (node (ref "D6") (pin "2") (pinfunction "2_2") (pintype "bidirectional"))
      (node (ref "J3") (pin "4") (pinfunction "4_4") (pintype "bidirectional"))
      (node (ref "J7") (pin "4") (pinfunction "4_4") (pintype "bidirectional"))
      (node (ref "R30") (pin "2") (pinfunction "2_2") (pintype "passive"))
      (node (ref "SW3") (pin "1") (pinfunction "P$1_1") (pintype "bidirectional"))
      (node (ref "U1") (pin "A8") (pinfunction "~{RESET}_A8") (pintype "bidirectional"))
    )
    (net (code "65") (name "MIC_OUTPUT") (class "Default")
      (node (ref "C55") (pin "2") (pinfunction "2_2") (pintype "passive"))
      (node (ref "U1") (pin "A4") (pinfunction "PC30/I14/AIN1.12_A4") (pintype "bidirectional"))
    )
    (net (code "66") (name "Net-(ANT2-Pad2)") (class "Default")
      (node (ref "ANT2") (pin "2") (pinfunction "2_2") (pintype "bidirectional"))
      (node (ref "C28") (pin "2") (pinfunction "2_2") (pintype "passive"))
      (node (ref "L3") (pin "1") (pinfunction "1_1") (pintype "passive"))
    )
    (net (code "67") (name "Net-(BUZ1-Pad-)") (class "Default")
      (node (ref "BUZ1") (pin "-") (pinfunction "-_-") (pintype "bidirectional"))
      (node (ref "D5") (pin "+") (pinfunction "+_+") (pintype "passive"))
      (node (ref "R6") (pin "1") (pinfunction "1_1") (pintype "passive"))
    )
    (net (code "68") (name "Net-(C27-Pad2)") (class "Default")
      (node (ref "C27") (pin "2") (pinfunction "2_2") (pintype "passive"))
      (node (ref "L3") (pin "2") (pinfunction "2_2") (pintype "passive"))
      (node (ref "U10") (pin "31") (pinfunction "31_31") (pintype "bidirectional"))
    )
    (net (code "69") (name "Net-(C34-Pad2)") (class "Default")
      (node (ref "C34") (pin "2") (pinfunction "2_2") (pintype "passive"))
      (node (ref "R23") (pin "1") (pinfunction "1_1") (pintype "passive"))
      (node (ref "R24") (pin "2") (pinfunction "2_2") (pintype "passive"))
    )
    (net (code "70") (name "Net-(C35-Pad1)") (class "Default")
      (node (ref "C35") (pin "1") (pinfunction "1_1") (pintype "passive"))
      (node (ref "R30") (pin "1") (pinfunction "1_1") (pintype "passive"))
      (node (ref "R9") (pin "1") (pinfunction "1_1") (pintype "passive"))
    )
    (net (code "71") (name "Net-(D7-+)") (class "Default")
      (node (ref "D7") (pin "1") (pinfunction "+_1") (pintype "passive"))
      (node (ref "R51") (pin "2") (pinfunction "2_2") (pintype "passive"))
    )
    (net (code "72") (name "Net-(D7--)") (class "Default")
      (node (ref "D7") (pin "2") (pinfunction "-_2") (pintype "passive"))
      (node (ref "Q3") (pin "3") (pinfunction "D_3") (pintype "passive"))
    )
    (net (code "73") (name "Net-(D10-Pad-)") (class "Default")
      (node (ref "D10") (pin "-") (pinfunction "-_-") (pintype "passive"))
      (node (ref "R83") (pin "1") (pinfunction "1_1") (pintype "passive"))
    )
    (net (code "74") (name "Net-(J1-DATA1)") (class "Default")
      (node (ref "D15") (pin "1") (pinfunction "14_1") (pintype "bidirectional"))
      (node (ref "D15") (pin "14") (pinfunction "14_14") (pintype "bidirectional"))
      (node (ref "J1") (pin "8") (pinfunction "DATA1_8") (pintype "bidirectional"))
      (node (ref "R60") (pin "1") (pinfunction "1_1") (pintype "passive"))
    )
    (net (code "75") (name "Net-(J1-DATA2)") (class "Default")
      (node (ref "D15") (pin "7") (pinfunction "8_7") (pintype "bidirectional"))
      (node (ref "D15") (pin "8") (pinfunction "8_8") (pintype "bidirectional"))
      (node (ref "J1") (pin "1") (pinfunction "DATA2_1") (pintype "bidirectional"))
      (node (ref "R64") (pin "1") (pinfunction "1_1") (pintype "passive"))
    )
    (net (code "76") (name "Net-(J1-DI)") (class "Default")
      (node (ref "D15") (pin "11") (pinfunction "11_11") (pintype "bidirectional"))
      (node (ref "D15") (pin "4") (pinfunction "11_4") (pintype "bidirectional"))
      (node (ref "J1") (pin "3") (pinfunction "DI_3") (pintype "bidirectional"))
      (node (ref "R45") (pin "1") (pinfunction "1_1") (pintype "passive"))
    )
    (net (code "77") (name "Net-(J1-DO)") (class "Default")
      (node (ref "D15") (pin "13") (pinfunction "13_13") (pintype "bidirectional"))
      (node (ref "D15") (pin "2") (pinfunction "13_2") (pintype "bidirectional"))
      (node (ref "J1") (pin "7") (pinfunction "DO_7") (pintype "bidirectional"))
      (node (ref "R43") (pin "1") (pinfunction "1_1") (pintype "passive"))
    )
    (net (code "78") (name "Net-(J1-SCLK)") (class "Default")
      (node (ref "D15") (pin "12") (pinfunction "12_12") (pintype "bidirectional"))
      (node (ref "D15") (pin "3") (pinfunction "12_3") (pintype "bidirectional"))
      (node (ref "J1") (pin "5") (pinfunction "SCLK_5") (pintype "bidirectional"))
      (node (ref "R44") (pin "1") (pinfunction "1_1") (pintype "passive"))
    )
    (net (code "79") (name "Net-(LED1-+)") (class "Default")
      (node (ref "LED1") (pin "1") (pinfunction "+_1") (pintype "passive"))
      (node (ref "R31") (pin "2") (pinfunction "2_2") (pintype "passive"))
    )
    (net (code "80") (name "Net-(MIC1-+)") (class "Default")
      (node (ref "C34") (pin "1") (pinfunction "1_1") (pintype "passive"))
      (node (ref "MIC1") (pin "1") (pinfunction "+_1") (pintype "bidirectional"))
      (node (ref "R22") (pin "2") (pinfunction "2_2") (pintype "passive"))
    )
    (net (code "81") (name "Net-(Q1-D)") (class "Default")
      (node (ref "Q1") (pin "3") (pinfunction "D_3") (pintype "passive"))
      (node (ref "R46") (pin "2") (pinfunction "2_2") (pintype "passive"))
    )
    (net (code "82") (name "Net-(Q1-G)") (class "Default")
      (node (ref "Q1") (pin "1") (pinfunction "G_1") (pintype "passive"))
      (node (ref "R16") (pin "1") (pinfunction "1_1") (pintype "passive"))
      (node (ref "R17") (pin "1") (pinfunction "1_1") (pintype "passive"))
    )
    (net (code "83") (name "Net-(Q2-D)") (class "Default")
      (node (ref "C4") (pin "2") (pinfunction "2_2") (pintype "passive"))
      (node (ref "C5") (pin "2") (pinfunction "2_2") (pintype "passive"))
      (node (ref "F1") (pin "2") (pinfunction "2_2") (pintype "bidirectional"))
      (node (ref "Q2") (pin "3") (pinfunction "D_3") (pintype "passive"))
    )
    (net (code "84") (name "Net-(Q2-G)") (class "Default")
      (node (ref "Q2") (pin "1") (pinfunction "G_1") (pintype "passive"))
      (node (ref "R19") (pin "1") (pinfunction "1_1") (pintype "passive"))
      (node (ref "R20") (pin "2") (pinfunction "2_2") (pintype "passive"))
      (node (ref "U9") (pin "4") (pinfunction "Y_4") (pintype "bidirectional"))
    )
    (net (code "85") (name "Net-(Q3-G)") (class "Default")
      (node (ref "Q3") (pin "1") (pinfunction "G_1") (pintype "passive"))
      (node (ref "R52") (pin "2") (pinfunction "2_2") (pintype "passive"))
      (node (ref "R53") (pin "2") (pinfunction "2_2") (pintype "passive"))
    )
    (net (code "86") (name "Net-(Q4-D)") (class "Default")
      (node (ref "Q4") (pin "3") (pinfunction "D_3") (pintype "passive"))
      (node (ref "R6") (pin "2") (pinfunction "2_2") (pintype "passive"))
    )
    (net (code "87") (name "Net-(Q4-G)") (class "Default")
      (node (ref "Q4") (pin "1") (pinfunction "G_1") (pintype "passive"))
      (node (ref "R5") (pin "2") (pinfunction "2_2") (pintype "passive"))
      (node (ref "R7") (pin "2") (pinfunction "2_2") (pintype "passive"))
    )
    (net (code "88") (name "Net-(Q7-G)") (class "Default")
      (node (ref "Q7") (pin "1") (pinfunction "G_1") (pintype "passive"))
      (node (ref "Q8") (pin "3") (pinfunction "D_3") (pintype "passive"))
      (node (ref "R91") (pin "1") (pinfunction "1_1") (pintype "passive"))
      (node (ref "SW3") (pin "2") (pinfunction "P$2_2") (pintype "bidirectional"))
    )
    (net (code "89") (name "Net-(Q8-G)") (class "Default")
      (node (ref "Q8") (pin "1") (pinfunction "G_1") (pintype "passive"))
      (node (ref "R29") (pin "1") (pinfunction "1_1") (pintype "passive"))
      (node (ref "SW3") (pin "4") (pinfunction "P$4_4") (pintype "bidirectional"))
    )
    (net (code "90") (name "Net-(Q10-G)") (class "Default")
      (node (ref "Q10") (pin "1") (pinfunction "G_1") (pintype "passive"))
      (node (ref "Q11") (pin "3") (pinfunction "C_3") (pintype "passive"))
      (node (ref "R97") (pin "2") (pinfunction "2_2") (pintype "passive"))
    )
    (net (code "91") (name "Net-(Q11A-B)") (class "Default")
      (node (ref "Q11") (pin "2") (pinfunction "B_2") (pintype "passive"))
      (node (ref "Q11") (pin "5") (pinfunction "B_5") (pintype "passive"))
      (node (ref "Q11") (pin "6") (pinfunction "C_6") (pintype "passive"))
      (node (ref "R98") (pin "2") (pinfunction "2_2") (pintype "passive"))
    )
    (net (code "92") (name "Net-(Q12-D)") (class "Default")
      (node (ref "Q12") (pin "3") (pinfunction "D_3") (pintype "passive"))
      (node (ref "Q15") (pin "3") (pinfunction "D_3") (pintype "passive"))
    )
    (net (code "93") (name "Net-(Q12-G)") (class "Default")
      (node (ref "Q12") (pin "1") (pinfunction "G_1") (pintype "passive"))
      (node (ref "Q15") (pin "1") (pinfunction "G_1") (pintype "passive"))
      (node (ref "R95") (pin "2") (pinfunction "2_2") (pintype "passive"))
      (node (ref "R96") (pin "1") (pinfunction "1_1") (pintype "passive"))
      (node (ref "R99") (pin "1") (pinfunction "1_1") (pintype "passive"))
    )
    (net (code "94") (name "Net-(Q13-D)") (class "Default")
      (node (ref "Q13") (pin "3") (pinfunction "D_3") (pintype "passive"))
      (node (ref "R83") (pin "2") (pinfunction "2_2") (pintype "passive"))
    )
    (net (code "95") (name "Net-(Q13-G)") (class "Default")
      (node (ref "Q13") (pin "1") (pinfunction "G_1") (pintype "passive"))
      (node (ref "R47") (pin "1") (pinfunction "1_1") (pintype "passive"))
      (node (ref "R80") (pin "1") (pinfunction "1_1") (pintype "passive"))
    )
    (net (code "96") (name "Net-(Q14-D)") (class "Default")
      (node (ref "Q14") (pin "3") (pinfunction "D_3") (pintype "passive"))
      (node (ref "Q9") (pin "3") (pinfunction "D_3") (pintype "passive"))
    )
    (net (code "97") (name "Net-(Q14-G)") (class "Default")
      (node (ref "Q14") (pin "1") (pinfunction "G_1") (pintype "passive"))
      (node (ref "Q16") (pin "3") (pinfunction "D_3") (pintype "passive"))
      (node (ref "Q9") (pin "1") (pinfunction "G_1") (pintype "passive"))
      (node (ref "R93") (pin "2") (pinfunction "2_2") (pintype "passive"))
      (node (ref "R94") (pin "1") (pinfunction "1_1") (pintype "passive"))
    )
    (net (code "98") (name "Net-(Q16-G)") (class "Default")
      (node (ref "Q16") (pin "1") (pinfunction "G_1") (pintype "passive"))
      (node (ref "R100") (pin "2") (pinfunction "2_2") (pintype "passive"))
      (node (ref "R88") (pin "2") (pinfunction "2_2") (pintype "passive"))
    )
    (net (code "99") (name "Net-(R10-Pad2)") (class "Default")
      (node (ref "R10") (pin "2") (pinfunction "2_2") (pintype "passive"))
      (node (ref "U10") (pin "22") (pinfunction "22_22") (pintype "bidirectional"))
    )
    (net (code "100") (name "Net-(R46-Pad1)") (class "Default")
      (node (ref "R46") (pin "1") (pinfunction "1_1") (pintype "passive"))
      (node (ref "U4") (pin "11") (pinfunction "LEDK_11") (pintype "bidirectional"))
      (node (ref "U4") (pin "12") (pinfunction "LEDK_12") (pintype "bidirectional"))
      (node (ref "U4") (pin "13") (pinfunction "LEDK_13") (pintype "bidirectional"))
      (node (ref "U4") (pin "14") (pinfunction "LEDK_14") (pintype "bidirectional"))
    )
    (net (code "101") (name "Net-(R65-Pad2)") (class "Default")
      (node (ref "R65") (pin "2") (pinfunction "2_2") (pintype "passive"))
      (node (ref "U10") (pin "23") (pinfunction "23_23") (pintype "bidirectional"))
    )
    (net (code "102") (name "Net-(R66-Pad1)") (class "Default")
      (node (ref "R66") (pin "1") (pinfunction "1_1") (pintype "passive"))
      (node (ref "U10") (pin "7") (pinfunction "7_7") (pintype "bidirectional"))
    )
    (net (code "103") (name "Net-(R67-Pad1)") (class "Default")
      (node (ref "R67") (pin "1") (pinfunction "1_1") (pintype "passive"))
      (node (ref "U10") (pin "10") (pinfunction "10_10") (pintype "bidirectional"))
    )
    (net (code "104") (name "Net-(R71-Pad1)") (class "Default")
      (node (ref "R71") (pin "1") (pinfunction "1_1") (pintype "passive"))
      (node (ref "R72") (pin "2") (pinfunction "2_2") (pintype "passive"))
    )
    (net (code "105") (name "Net-(R77-Pad2)") (class "Default")
      (node (ref "R77") (pin "2") (pinfunction "2_2") (pintype "passive"))
      (node (ref "R79") (pin "1") (pinfunction "1_1") (pintype "passive"))
      (node (ref "U8") (pin "2-1") (pinfunction "2_2-1") (pintype "bidirectional"))
      (node (ref "U8") (pin "2-2") (pinfunction "2_2-2") (pintype "bidirectional"))
    )
    (net (code "106") (name "Net-(R81-Pad1)") (class "Default")
      (node (ref "R81") (pin "1") (pinfunction "1_1") (pintype "passive"))
      (node (ref "U10") (pin "9") (pinfunction "9_9") (pintype "bidirectional"))
    )
    (net (code "107") (name "Net-(R82-Pad1)") (class "Default")
      (node (ref "R82") (pin "1") (pinfunction "1_1") (pintype "passive"))
      (node (ref "U10") (pin "8") (pinfunction "8_8") (pintype "bidirectional"))
    )
    (net (code "108") (name "Net-(U1A-VDDCORE)") (class "Default")
      (node (ref "C36") (pin "1") (pinfunction "1_1") (pintype "passive"))
      (node (ref "C37") (pin "1") (pinfunction "1_1") (pintype "passive"))
      (node (ref "C38") (pin "1") (pinfunction "1_1") (pintype "passive"))
      (node (ref "L6") (pin "2") (pinfunction "2_2") (pintype "passive"))
      (node (ref "U1") (pin "A7") (pinfunction "VDDCORE_A7") (pintype "bidirectional"))
    )
    (net (code "109") (name "Net-(U1A-VSW)") (class "Default")
      (node (ref "L6") (pin "1") (pinfunction "1_1") (pintype "passive"))
      (node (ref "U1") (pin "A6") (pinfunction "VSW_A6") (pintype "bidirectional"))
    )
    (net (code "110") (name "Net-(U1B-PA00{slash}I0{slash}SERCOM1.0{slash}TC2.0)") (class "Default")
      (node (ref "C49") (pin "2") (pinfunction "2_2") (pintype "passive"))
      (node (ref "U1") (pin "A1") (pinfunction "PA00/I0/SERCOM1.0/TC2.0_A1") (pintype "bidirectional"))
      (node (ref "X2") (pin "2") (pinfunction "2_2") (pintype "passive"))
    )
    (net (code "111") (name "Net-(U1B-PA01{slash}I1{slash}SERCOM1.1{slash}TC2.1)") (class "Default")
      (node (ref "C50") (pin "2") (pinfunction "2_2") (pintype "passive"))
      (node (ref "U1") (pin "B1") (pinfunction "PA01/I1/SERCOM1.1/TC2.1_B1") (pintype "bidirectional"))
      (node (ref "X2") (pin "1") (pinfunction "1_1") (pintype "passive"))
    )
    (net (code "112") (name "Net-(U1B-PA03{slash}I3{slash}VREFA{slash}AIN0.1)") (class "Default")
      (node (ref "R12") (pin "2") (pinfunction "2_2") (pintype "passive"))
      (node (ref "U1") (pin "F2") (pinfunction "PA03/I3/VREFA/AIN0.1_F2") (pintype "bidirectional"))
    )
    (net (code "113") (name "Net-(U1C-PC00{slash}I1{slash}ADC1.10)") (class "Default")
      (node (ref "R50") (pin "1") (pinfunction "1_1") (pintype "passive"))
      (node (ref "U1") (pin "C1") (pinfunction "PC00/I1/ADC1.10_C1") (pintype "bidirectional"))
    )
    (net (code "114") (name "Net-(U1C-PC22{slash}I6{slash}SERCOM1.0+3.1{slash}TCC0.6)") (class "Default")
      (node (ref "R69") (pin "1") (pinfunction "1_1") (pintype "passive"))
      (node (ref "U1") (pin "K15") (pinfunction "PC22/I6/SERCOM1.0+3.1/TCC0.6_K15") (pintype "bidirectional"))
    )
    (net (code "115") (name "Net-(U1C-PC23{slash}I7{slash}SERCOM1.1+3.0{slash}TCC0.7)") (class "Default")
      (node (ref "R68") (pin "1") (pinfunction "1_1") (pintype "passive"))
      (node (ref "U1") (pin "J14") (pinfunction "PC23/I7/SERCOM1.1+3.0/TCC0.7_J14") (pintype "bidirectional"))
    )
    (net (code "116") (name "Net-(U2A-+IN1)") (class "Default")
      (node (ref "R24") (pin "1") (pinfunction "1_1") (pintype "passive"))
      (node (ref "U2") (pin "3") (pinfunction "+IN1_3") (pintype "input"))
    )
    (net (code "117") (name "Net-(U2A--IN1)") (class "Default")
      (node (ref "R25") (pin "2") (pinfunction "2_2") (pintype "passive"))
      (node (ref "R26") (pin "1") (pinfunction "1_1") (pintype "passive"))
      (node (ref "U2") (pin "2") (pinfunction "-IN1_2") (pintype "input"))
    )
    (net (code "118") (name "Net-(U2A-OUT1)") (class "Default")
      (node (ref "R26") (pin "2") (pinfunction "2_2") (pintype "passive"))
      (node (ref "U2") (pin "1") (pinfunction "OUT1_1") (pintype "output"))
      (node (ref "U2") (pin "5") (pinfunction "+IN2_5") (pintype "input"))
    )
    (net (code "119") (name "Net-(U2B--IN2)") (class "Default")
      (node (ref "R27") (pin "1") (pinfunction "1_1") (pintype "passive"))
      (node (ref "R28") (pin "2") (pinfunction "2_2") (pintype "passive"))
      (node (ref "U2") (pin "6") (pinfunction "-IN2_6") (pintype "input"))
    )
    (net (code "120") (name "Net-(U2B-OUT2)") (class "Default")
      (node (ref "C55") (pin "1") (pinfunction "1_1") (pintype "passive"))
      (node (ref "R27") (pin "2") (pinfunction "2_2") (pintype "passive"))
      (node (ref "U2") (pin "7") (pinfunction "OUT2_7") (pintype "output"))
    )
    (net (code "121") (name "Net-(U4-CS)") (class "Default")
      (node (ref "R74") (pin "1") (pinfunction "1_1") (pintype "passive"))
      (node (ref "U4") (pin "5") (pinfunction "CS_5") (pintype "bidirectional"))
    )
    (net (code "122") (name "Net-(U4-D{slash}C)") (class "Default")
      (node (ref "C13") (pin "1") (pinfunction "1_1") (pintype "passive"))
      (node (ref "R57") (pin "1") (pinfunction "1_1") (pintype "passive"))
      (node (ref "U4") (pin "4") (pinfunction "D/C_4") (pintype "bidirectional"))
    )
    (net (code "123") (name "Net-(U4-SCL)") (class "Default")
      (node (ref "C12") (pin "1") (pinfunction "1_1") (pintype "passive"))
      (node (ref "R35") (pin "1") (pinfunction "1_1") (pintype "passive"))
      (node (ref "U4") (pin "3") (pinfunction "SCL_3") (pintype "bidirectional"))
    )
    (net (code "124") (name "Net-(U4-SDA)") (class "Default")
      (node (ref "C43") (pin "1") (pinfunction "1_1") (pintype "passive"))
      (node (ref "R75") (pin "1") (pinfunction "1_1") (pintype "passive"))
      (node (ref "U4") (pin "6") (pinfunction "SDA_6") (pintype "bidirectional"))
    )
    (net (code "125") (name "Net-(U4-SDO)") (class "Default")
      (node (ref "C42") (pin "1") (pinfunction "1_1") (pintype "passive"))
      (node (ref "R76") (pin "1") (pinfunction "1_1") (pintype "passive"))
      (node (ref "U4") (pin "7") (pinfunction "SDO_7") (pintype "bidirectional"))
    )
    (net (code "126") (name "Net-(U4-XL)") (class "Default")
      (node (ref "R39") (pin "2") (pinfunction "2_2") (pintype "passive"))
      (node (ref "U4") (pin "15") (pinfunction "XL_15") (pintype "bidirectional"))
    )
    (net (code "127") (name "Net-(U4-XR)") (class "Default")
      (node (ref "R41") (pin "2") (pinfunction "2_2") (pintype "passive"))
      (node (ref "U4") (pin "17") (pinfunction "XR_17") (pintype "bidirectional"))
    )
    (net (code "128") (name "Net-(U4-YD)") (class "Default")
      (node (ref "R42") (pin "2") (pinfunction "2_2") (pintype "passive"))
      (node (ref "U4") (pin "18") (pinfunction "YD_18") (pintype "bidirectional"))
    )
    (net (code "129") (name "Net-(U4-YU)") (class "Default")
      (node (ref "R40") (pin "2") (pinfunction "2_2") (pintype "passive"))
      (node (ref "U4") (pin "16") (pinfunction "YU_16") (pintype "bidirectional"))
    )
    (net (code "130") (name "Net-(U9-A)") (class "Default")
      (node (ref "R18") (pin "2") (pinfunction "2_2") (pintype "passive"))
      (node (ref "R21") (pin "1") (pinfunction "1_1") (pintype "passive"))
      (node (ref "U9") (pin "1") (pinfunction "~{OE}_1") (pintype "bidirectional"))
      (node (ref "U9") (pin "2") (pinfunction "A_2") (pintype "bidirectional"))
    )
    (net (code "131") (name "Net-(U12-FB)") (class "Default")
      (node (ref "R70") (pin "1") (pinfunction "1_1") (pintype "passive"))
      (node (ref "R71") (pin "2") (pinfunction "2_2") (pintype "passive"))
      (node (ref "U12") (pin "7") (pinfunction "FB_7") (pintype "bidirectional"))
    )
    (net (code "132") (name "Net-(U12-SW)") (class "Default")
      (node (ref "L5") (pin "1") (pinfunction "1_1") (pintype "passive"))
      (node (ref "U12") (pin "3") (pinfunction "SW_3") (pintype "bidirectional"))
    )
    (net (code "133") (name "Net-(USB1-A4{slash}B9{slash}VBUS)") (class "Default")
      (node (ref "D2") (pin "1") (pinfunction "1_1") (pintype "bidirectional"))
      (node (ref "F1") (pin "1") (pinfunction "1_1") (pintype "bidirectional"))
      (node (ref "USB1") (pin "A4_B9") (pinfunction "A4/B9/VBUS_A4_B9") (pintype "bidirectional"))
      (node (ref "USB1") (pin "B4_A9") (pinfunction "B4/A9/VBUS_B4_A9") (pintype "bidirectional"))
    )
    (net (code "134") (name "Net-(USB1-A5{slash}CC1)") (class "Default")
      (node (ref "R1") (pin "2") (pinfunction "2_2") (pintype "passive"))
      (node (ref "USB1") (pin "A5") (pinfunction "A5/CC1_A5") (pintype "bidirectional"))
    )
    (net (code "135") (name "Net-(USB1-B5{slash}CC2)") (class "Default")
      (node (ref "R2") (pin "2") (pinfunction "2_2") (pintype "passive"))
      (node (ref "USB1") (pin "B5") (pinfunction "B5/CC2_B5") (pintype "bidirectional"))
    )
    (net (code "136") (name "Net-(X4-X1)") (class "Default")
      (node (ref "C52") (pin "1") (pinfunction "1_1") (pintype "passive"))
      (node (ref "R8") (pin "2") (pinfunction "2_2") (pintype "passive"))
      (node (ref "X4") (pin "1") (pinfunction "X1_1") (pintype "bidirectional"))
    )
    (net (code "137") (name "PWR_EN") (class "Default")
      (node (ref "Q7") (pin "3") (pinfunction "D_3") (pintype "passive"))
      (node (ref "R73") (pin "1") (pinfunction "1_1") (pintype "passive"))
      (node (ref "R78") (pin "2") (pinfunction "2_2") (pintype "passive"))
      (node (ref "R90") (pin "2") (pinfunction "2_2") (pintype "passive"))
      (node (ref "U12") (pin "8") (pinfunction "EN_8") (pintype "bidirectional"))
      (node (ref "U13") (pin "3") (pinfunction "~{SHUTDOWN}_3") (pintype "bidirectional"))
    )
    (net (code "138") (name "RPI_3V3") (class "Default")
      (node (ref "Q10") (pin "3") (pinfunction "D_3") (pintype "passive"))
      (node (ref "Q11") (pin "1") (pinfunction "E_1") (pintype "passive"))
      (node (ref "Q15") (pin "2") (pinfunction "S_2") (pintype "passive"))
      (node (ref "U3") (pin "1") (pinfunction "3V3_1") (pintype "power_in"))
      (node (ref "U3") (pin "17") (pinfunction "3V3_17") (pintype "power_in"))
    )
    (net (code "139") (name "RPI_5V") (class "Default")
      (node (ref "D9") (pin "+") (pinfunction "+_+") (pintype "passive"))
      (node (ref "Q14") (pin "2") (pinfunction "S_2") (pintype "passive"))
      (node (ref "R20") (pin "1") (pinfunction "1_1") (pintype "passive"))
      (node (ref "U3") (pin "2") (pinfunction "5V0_2") (pintype "power_in"))
      (node (ref "U3") (pin "4") (pinfunction "5V0_4") (pintype "power_in"))
    )
    (net (code "140") (name "RTL8720D_CHIP_PU") (class "Default")
      (node (ref "C9") (pin "1") (pinfunction "1_1") (pintype "passive"))
      (node (ref "J2") (pin "5") (pinfunction "5_5") (pintype "bidirectional"))
      (node (ref "J3") (pin "10") (pinfunction "10_10") (pintype "bidirectional"))
      (node (ref "R11") (pin "1") (pinfunction "1_1") (pintype "passive"))
      (node (ref "U1") (pin "P15") (pinfunction "PA18/I2/SERCOM1+3.2/TC3.0+TCC1.2+0.6/PTC_P15") (pintype "bidirectional"))
      (node (ref "U10") (pin "24") (pinfunction "24_24") (pintype "bidirectional"))
    )
    (net (code "141") (name "RTL8720D_HSPI_CLK") (class "Default")
      (node (ref "R10") (pin "1") (pinfunction "1_1") (pintype "passive"))
      (node (ref "R66") (pin "2") (pinfunction "2_2") (pintype "passive"))
      (node (ref "U1") (pin "B13") (pinfunction "PB25/SERCOM0.1+2.0/QDI.2_B13") (pintype "bidirectional"))
    )
    (net (code "142") (name "RTL8720D_HSPI_CS") (class "Default")
      (node (ref "R82") (pin "2") (pinfunction "2_2") (pintype "passive"))
      (node (ref "U1") (pin "B10") (pinfunction "PC25/I9/SERCOM0+2.3/TRACEDATA.2_B10") (pintype "bidirectional"))
    )
    (net (code "143") (name "RTL8720D_HSPI_MISO") (class "Default")
      (node (ref "R81") (pin "2") (pinfunction "2_2") (pintype "passive"))
      (node (ref "U1") (pin "A11") (pinfunction "PC24/I8/SERCOM0+2.2/TRACEDATA.3_A11") (pintype "bidirectional"))
    )
    (net (code "144") (name "RTL8720D_HSPI_MOSI") (class "Default")
      (node (ref "R65") (pin "1") (pinfunction "1_1") (pintype "passive"))
      (node (ref "R67") (pin "2") (pinfunction "2_2") (pintype "passive"))
      (node (ref "U1") (pin "B14") (pinfunction "PB24/I8/SERCOM0.0+2.1/QDI.1_B14") (pintype "bidirectional"))
    )
    (net (code "145") (name "RTL8720D_RXD") (class "Default")
      (node (ref "J2") (pin "4") (pinfunction "4_4") (pintype "bidirectional"))
      (node (ref "J3") (pin "9") (pinfunction "9_9") (pintype "bidirectional"))
      (node (ref "R69") (pin "2") (pinfunction "2_2") (pintype "passive"))
      (node (ref "U10") (pin "26") (pinfunction "26_26") (pintype "bidirectional"))
    )
    (net (code "146") (name "RTL8720D_TXD") (class "Default")
      (node (ref "J2") (pin "3") (pinfunction "3_3") (pintype "bidirectional"))
      (node (ref "J3") (pin "8") (pinfunction "8_8") (pintype "bidirectional"))
      (node (ref "R68") (pin "2") (pinfunction "2_2") (pintype "passive"))
      (node (ref "U10") (pin "25") (pinfunction "25_25") (pintype "bidirectional"))
    )
    (net (code "147") (name "RXD") (class "Default")
      (node (ref "U1") (pin "B12") (pinfunction "PB27/I13/SERCOM2.1+4.0/TCC1.3_B12") (pintype "bidirectional"))
      (node (ref "U3") (pin "10") (pinfunction "RXD0/GPIO15_10") (pintype "bidirectional"))
    )
    (net (code "148") (name "SD_CS") (class "Default")
      (node (ref "D15") (pin "6") (pinfunction "9_6") (pintype "bidirectional"))
      (node (ref "D15") (pin "9") (pinfunction "9_9") (pintype "bidirectional"))
      (node (ref "J1") (pin "2") (pinfunction "CS_2") (pintype "bidirectional"))
      (node (ref "R63") (pin "1") (pinfunction "1_1") (pintype "passive"))
      (node (ref "U1") (pin "L14") (pinfunction "PC19/I3/SERCOM6+0.3/TCC0.3_L14") (pintype "bidirectional"))
    )
    (net (code "149") (name "SD_DET") (class "Default")
      (node (ref "D8") (pin "2") (pinfunction "2_2") (pintype "bidirectional"))
      (node (ref "J1") (pin "9") (pinfunction "CDN_9") (pintype "bidirectional"))
      (node (ref "R36") (pin "1") (pinfunction "1_1") (pintype "passive"))
      (node (ref "U1") (pin "H14") (pinfunction "PD21/I11/SERCOM1+3.3/TCC1.1/SDHC1.SDWP_H14") (pintype "bidirectional"))
    )
    (net (code "150") (name "SD_MISO") (class "Default")
      (node (ref "R43") (pin "2") (pinfunction "2_2") (pintype "passive"))
      (node (ref "R61") (pin "1") (pinfunction "1_1") (pintype "passive"))
      (node (ref "U1") (pin "M15") (pinfunction "PC18/I2/SERCOM6.2+0.2/TCC0.2/QDI.2_M15") (pintype "bidirectional"))
    )
    (net (code "151") (name "SD_MOSI") (class "Default")
      (node (ref "R45") (pin "2") (pinfunction "2_2") (pintype "passive"))
      (node (ref "R62") (pin "1") (pinfunction "1_1") (pintype "passive"))
      (node (ref "U1") (pin "N15") (pinfunction "PC16/I0/SERCOM6.0+0.1/TCC0/QDI.0_N15") (pintype "bidirectional"))
    )
    (net (code "152") (name "SD_SCK") (class "Default")
      (node (ref "R44") (pin "2") (pinfunction "2_2") (pintype "passive"))
      (node (ref "U1") (pin "M14") (pinfunction "PC17/I1/SERCOM6.1+0.0/TCC0.1/QDI.1_M14") (pintype "bidirectional"))
    )
    (net (code "153") (name "SPI_CS") (class "Default")
      (node (ref "U1") (pin "B3") (pinfunction "PB01/I1/AIN0.13/SERCOM5.3/TC7.1/PTC_B3") (pintype "bidirectional"))
      (node (ref "U3") (pin "24") (pinfunction "~{CE0}/GPIO8_24") (pintype "bidirectional"))
    )
    (net (code "154") (name "SPI_MISO") (class "Default")
      (node (ref "J6") (pin "2") (pinfunction "2_2") (pintype "bidirectional"))
      (node (ref "U1") (pin "A3") (pinfunction "PB00/I0/AIN0.12/SERCOM5.2/TC7.0/PTC_A3") (pintype "bidirectional"))
      (node (ref "U3") (pin "21") (pinfunction "GPIO9/MISO_21") (pintype "bidirectional"))
    )
    (net (code "155") (name "SPI_MOSI") (class "Default")
      (node (ref "J6") (pin "1") (pinfunction "1_1") (pintype "bidirectional"))
      (node (ref "U1") (pin "A2") (pinfunction "PB02/I2/AIN0.14/SERCOM5.0/TC6.0+TCC2.2/PTC_A2") (pintype "bidirectional"))
      (node (ref "U3") (pin "19") (pinfunction "GPIO10/MOSI_19") (pintype "bidirectional"))
    )
    (net (code "156") (name "SPI_SCK") (class "Default")
      (node (ref "J6") (pin "3") (pinfunction "3_3") (pintype "bidirectional"))
      (node (ref "U1") (pin "B2") (pinfunction "PB03/I3/AIN0.15/SERCOM5.1/TC6.1/PTC_B2") (pintype "bidirectional"))
      (node (ref "U3") (pin "23") (pinfunction "GPIO11/SCLK_23") (pintype "bidirectional"))
    )
    (net (code "157") (name "SWDCLK") (class "Default")
      (node (ref "J3") (pin "1") (pinfunction "1_1") (pintype "bidirectional"))
      (node (ref "J7") (pin "1") (pinfunction "1_1") (pintype "bidirectional"))
      (node (ref "R33") (pin "2") (pinfunction "2_2") (pintype "passive"))
      (node (ref "R38") (pin "2") (pinfunction "2_2") (pintype "passive"))
      (node (ref "U1") (pin "B7") (pinfunction "PA30/I14/SERCOM1.2/SWCLK_B7") (pintype "bidirectional"))
    )
    (net (code "158") (name "SWDIO") (class "Default")
      (node (ref "J3") (pin "2") (pinfunction "2_2") (pintype "bidirectional"))
      (node (ref "J7") (pin "2") (pinfunction "2_2") (pintype "bidirectional"))
      (node (ref "R34") (pin "2") (pinfunction "2_2") (pintype "passive"))
      (node (ref "R54") (pin "1") (pinfunction "1_1") (pintype "passive"))
      (node (ref "U1") (pin "B6") (pinfunction "PA31/I15/SERCOM1.3/SWDIO_B6") (pintype "bidirectional"))
    )
    (net (code "159") (name "SWITCH_B") (class "Default")
      (node (ref "R86") (pin "1") (pinfunction "1_1") (pintype "passive"))
      (node (ref "SW1") (pin "4") (pinfunction "4_4") (pintype "bidirectional"))
      (node (ref "U1") (pin "R8") (pinfunction "PD12/I7/TCC0.5_R8") (pintype "bidirectional"))
    )
    (net (code "160") (name "SWITCH_U") (class "Default")
      (node (ref "R87") (pin "1") (pinfunction "1_1") (pintype "passive"))
      (node (ref "SW1") (pin "6") (pinfunction "6_6") (pintype "bidirectional"))
      (node (ref "U1") (pin "J15") (pinfunction "PD20/I10/SERCOM1+3.2/TCC1.0/SDHC1.SDCD_J15") (pintype "bidirectional"))
    )
    (net (code "161") (name "SWITCH_X") (class "Default")
      (node (ref "R37") (pin "1") (pinfunction "1_1") (pintype "passive"))
      (node (ref "SW1") (pin "1") (pinfunction "1_1") (pintype "bidirectional"))
      (node (ref "U1") (pin "R6") (pinfunction "PD08/I3/SERCOM7.0+6.1/TCC0.1_R6") (pintype "bidirectional"))
    )
    (net (code "162") (name "SWITCH_Y") (class "Default")
      (node (ref "R85") (pin "1") (pinfunction "1_1") (pintype "passive"))
      (node (ref "SW1") (pin "3") (pinfunction "3_3") (pintype "bidirectional"))
      (node (ref "U1") (pin "P8") (pinfunction "PD09/I4/SERCOM7.1+6.0/TCC0.2_P8") (pintype "bidirectional"))
    )
    (net (code "163") (name "SWITCH_Z") (class "Default")
      (node (ref "R84") (pin "1") (pinfunction "1_1") (pintype "passive"))
      (node (ref "SW1") (pin "2") (pinfunction "2_2") (pintype "bidirectional"))
      (node (ref "U1") (pin "R7") (pinfunction "PD10/I5/SERCOM7+6.2/TCC0.3_R7") (pintype "bidirectional"))
    )
    (net (code "164") (name "SWO") (class "Default")
      (node (ref "J3") (pin "3") (pinfunction "3_3") (pintype "bidirectional"))
      (node (ref "J7") (pin "3") (pinfunction "3_3") (pintype "bidirectional"))
      (node (ref "U1") (pin "A5") (pinfunction "PB30/I14/SERCOM5.1/TC0.0+TCC4.0+0.6/SWO_A5") (pintype "bidirectional"))
    )
    (net (code "165") (name "SYNC") (class "Default")
      (node (ref "R102") (pin "1") (pinfunction "1_1") (pintype "passive"))
      (node (ref "U1") (pin "N14") (pinfunction "PA19/I3/SERCOM1+3.3/TC3.1+TCC1.3+0.7/PT_N14") (pintype "bidirectional"))
      (node (ref "U10") (pin "3") (pinfunction "3_3") (pintype "bidirectional"))
    )
    (net (code "166") (name "TXD") (class "Default")
      (node (ref "U1") (pin "A13") (pinfunction "PB26/I12/SERCOM2.0+4.1/TCC1.3_A13") (pintype "bidirectional"))
      (node (ref "U3") (pin "8") (pinfunction "TXD0/GPIO14_8") (pintype "bidirectional"))
    )
    (net (code "167") (name "USB_5V") (class "Default")
      (node (ref "C3") (pin "2") (pinfunction "2_2") (pintype "passive"))
      (node (ref "C66") (pin "2") (pinfunction "2_2") (pintype "passive"))
      (node (ref "C67") (pin "2") (pinfunction "2_2") (pintype "passive"))
      (node (ref "C8") (pin "1") (pinfunction "1_1") (pintype "passive"))
      (node (ref "D9") (pin "-") (pinfunction "-_-") (pintype "passive"))
      (node (ref "J6") (pin "19") (pinfunction "19_19") (pintype "bidirectional"))
      (node (ref "J6") (pin "20") (pinfunction "20_20") (pintype "bidirectional"))
      (node (ref "Q2") (pin "2") (pinfunction "S_2") (pintype "passive"))
      (node (ref "Q7") (pin "2") (pinfunction "S_2") (pintype "passive"))
      (node (ref "Q8") (pin "2") (pinfunction "S_2") (pintype "passive"))
      (node (ref "Q9") (pin "2") (pinfunction "S_2") (pintype "passive"))
      (node (ref "R29") (pin "2") (pinfunction "2_2") (pintype "passive"))
      (node (ref "R73") (pin "2") (pinfunction "2_2") (pintype "passive"))
      (node (ref "R90") (pin "1") (pinfunction "1_1") (pintype "passive"))
      (node (ref "R94") (pin "2") (pinfunction "2_2") (pintype "passive"))
      (node (ref "U12") (pin "2") (pinfunction "VIN_2") (pintype "bidirectional"))
      (node (ref "U13") (pin "1") (pinfunction "VIN_1") (pintype "bidirectional"))
    )
    (net (code "168") (name "USB_D+") (class "Default")
      (node (ref "R56") (pin "1") (pinfunction "1_1") (pintype "passive"))
      (node (ref "U1") (pin "B15") (pinfunction "PA25/19/SERCOM3+5.3/D+_B15") (pintype "bidirectional"))
    )
    (net (code "169") (name "USB_D-") (class "Default")
      (node (ref "R55") (pin "2") (pinfunction "2_2") (pintype "passive"))
      (node (ref "U1") (pin "C15") (pinfunction "PA24/I8/SERCOM3+5.2/D-_C15") (pintype "bidirectional"))
    )
    (net (code "170") (name "USB_HOST_EN") (class "Default")
      (node (ref "R21") (pin "2") (pinfunction "2_2") (pintype "passive"))
      (node (ref "U1") (pin "B8") (pinfunction "PA27/I11_B8") (pintype "bidirectional"))
    )
    (net (code "171") (name "USER_LED") (class "Default")
      (node (ref "R53") (pin "1") (pinfunction "1_1") (pintype "passive"))
      (node (ref "U1") (pin "R14") (pinfunction "PA15/I15/SERCOM2+4.3/TC3.1+TCC2.1+1.3_R14") (pintype "bidirectional"))
    )
    (net (code "172") (name "VCC3V3_8720") (class "Default")
      (node (ref "C1") (pin "2") (pinfunction "2_2") (pintype "passive"))
      (node (ref "C10") (pin "1") (pinfunction "1_1") (pintype "passive"))
      (node (ref "C2") (pin "2") (pinfunction "2_2") (pintype "passive"))
      (node (ref "C6") (pin "2") (pinfunction "2_2") (pintype "passive"))
      (node (ref "C7") (pin "1") (pinfunction "1_1") (pintype "passive"))
      (node (ref "J2") (pin "1") (pinfunction "1_1") (pintype "bidirectional"))
      (node (ref "R102") (pin "2") (pinfunction "2_2") (pintype "passive"))
      (node (ref "R103") (pin "2") (pinfunction "2_2") (pintype "passive"))
      (node (ref "R11") (pin "2") (pinfunction "2_2") (pintype "passive"))
      (node (ref "U10") (pin "16") (pinfunction "16_16") (pintype "bidirectional"))
      (node (ref "U13") (pin "5") (pinfunction "VOUT_5") (pintype "bidirectional"))
    )
    (net (code "173") (name "VCC3V3_MCU_A") (class "Default")
      (node (ref "C33") (pin "1") (pinfunction "1_1") (pintype "passive"))
      (node (ref "C60") (pin "1") (pinfunction "1_1") (pintype "passive"))
      (node (ref "L2") (pin "1") (pinfunction "1_1") (pintype "passive"))
      (node (ref "R12") (pin "1") (pinfunction "1_1") (pintype "passive"))
      (node (ref "R22") (pin "1") (pinfunction "1_1") (pintype "passive"))
      (node (ref "U1") (pin "G6") (pinfunction "VDDANA0_G6") (pintype "bidirectional"))
      (node (ref "U1") (pin "M2") (pinfunction "VDDANA1_M2") (pintype "bidirectional"))
      (node (ref "U2") (pin "8") (pinfunction "+V_8") (pintype "power_in"))
    )
    (net (code "174") (name "VCC3V3_MCU_D") (class "Default")
      (node (ref "C15") (pin "1") (pinfunction "1_1") (pintype "passive"))
      (node (ref "C16") (pin "1") (pinfunction "1_1") (pintype "passive"))
      (node (ref "C39") (pin "1") (pinfunction "1_1") (pintype "passive"))
      (node (ref "C40") (pin "1") (pinfunction "1_1") (pintype "passive"))
      (node (ref "C41") (pin "1") (pinfunction "1_1") (pintype "passive"))
      (node (ref "C48") (pin "1") (pinfunction "1_1") (pintype "passive"))
      (node (ref "C62") (pin "1") (pinfunction "1_1") (pintype "passive"))
      (node (ref "D1") (pin "2") (pinfunction "2_2") (pintype "bidirectional"))
      (node (ref "FB3") (pin "2") (pinfunction "2_2") (pintype "bidirectional"))
      (node (ref "J1") (pin "4") (pinfunction "VDD_4") (pintype "bidirectional"))
      (node (ref "J7") (pin "6") (pinfunction "6_6") (pintype "bidirectional"))
      (node (ref "R3") (pin "2") (pinfunction "2_2") (pintype "passive"))
      (node (ref "R32") (pin "2") (pinfunction "2_2") (pintype "passive"))
      (node (ref "R36") (pin "2") (pinfunction "2_2") (pintype "passive"))
      (node (ref "R37") (pin "2") (pinfunction "2_2") (pintype "passive"))
      (node (ref "R38") (pin "1") (pinfunction "1_1") (pintype "passive"))
      (node (ref "R4") (pin "2") (pinfunction "2_2") (pintype "passive"))
      (node (ref "R49") (pin "2") (pinfunction "2_2") (pintype "passive"))
      (node (ref "R51") (pin "1") (pinfunction "1_1") (pintype "passive"))
      (node (ref "R58") (pin "2") (pinfunction "2_2") (pintype "passive"))
      (node (ref "R59") (pin "2") (pinfunction "2_2") (pintype "passive"))
      (node (ref "R60") (pin "2") (pinfunction "2_2") (pintype "passive"))
      (node (ref "R61") (pin "2") (pinfunction "2_2") (pintype "passive"))
      (node (ref "R62") (pin "2") (pinfunction "2_2") (pintype "passive"))
      (node (ref "R63") (pin "2") (pinfunction "2_2") (pintype "passive"))
      (node (ref "R64") (pin "2") (pinfunction "2_2") (pintype "passive"))
      (node (ref "R84") (pin "2") (pinfunction "2_2") (pintype "passive"))
      (node (ref "R85") (pin "2") (pinfunction "2_2") (pintype "passive"))
      (node (ref "R86") (pin "2") (pinfunction "2_2") (pintype "passive"))
      (node (ref "R87") (pin "2") (pinfunction "2_2") (pintype "passive"))
      (node (ref "R9") (pin "2") (pinfunction "2_2") (pintype "passive"))
      (node (ref "U1") (pin "F10") (pinfunction "VDDIO5_F10") (pintype "bidirectional"))
      (node (ref "U1") (pin "F7") (pinfunction "VDDIO7_F7") (pintype "bidirectional"))
      (node (ref "U1") (pin "F8") (pinfunction "VDDIO6_F8") (pintype "bidirectional"))
      (node (ref "U1") (pin "H10") (pinfunction "VDDIO4_H10") (pintype "bidirectional"))
      (node (ref "U1") (pin "K10") (pinfunction "VDDIO3_K10") (pintype "bidirectional"))
      (node (ref "U1") (pin "K6") (pinfunction "VDDIOB1_K6") (pintype "bidirectional"))
      (node (ref "U1") (pin "K7") (pinfunction "VDDIOB2_K7") (pintype "bidirectional"))
      (node (ref "U14") (pin "8") (pinfunction "VCC_8") (pintype "bidirectional"))
    )
    (net (code "175") (name "VCC_3V3") (class "Default")
      (node (ref "BUZ1") (pin "+") (pinfunction "+_+") (pintype "bidirectional"))
      (node (ref "C11") (pin "2") (pinfunction "2_2") (pintype "passive"))
      (node (ref "C14") (pin "2") (pinfunction "2_2") (pintype "passive"))
      (node (ref "C32") (pin "1") (pinfunction "1_1") (pintype "passive"))
      (node (ref "C53") (pin "1") (pinfunction "1_1") (pintype "passive"))
      (node (ref "C54") (pin "1") (pinfunction "1_1") (pintype "passive"))
      (node (ref "C61") (pin "1") (pinfunction "1_1") (pintype "passive"))
      (node (ref "C63") (pin "+") (pinfunction "+_+") (pintype "passive"))
      (node (ref "C64") (pin "2") (pinfunction "2_2") (pintype "passive"))
      (node (ref "C65") (pin "2") (pinfunction "2_2") (pintype "passive"))
      (node (ref "D10") (pin "+") (pinfunction "+_+") (pintype "passive"))
      (node (ref "D5") (pin "-") (pinfunction "-_-") (pintype "passive"))
      (node (ref "FB2") (pin "1") (pinfunction "1_1") (pintype "bidirectional"))
      (node (ref "FB3") (pin "1") (pinfunction "1_1") (pintype "bidirectional"))
      (node (ref "J4") (pin "3") (pinfunction "3_3") (pintype "bidirectional"))
      (node (ref "J5") (pin "3") (pinfunction "3_3") (pintype "bidirectional"))
      (node (ref "J6") (pin "15") (pinfunction "15_15") (pintype "bidirectional"))
      (node (ref "J6") (pin "16") (pinfunction "16_16") (pintype "bidirectional"))
      (node (ref "L2") (pin "2") (pinfunction "2_2") (pintype "passive"))
      (node (ref "L5") (pin "2") (pinfunction "2_2") (pintype "passive"))
      (node (ref "Q10") (pin "2") (pinfunction "S_2") (pintype "passive"))
      (node (ref "Q11") (pin "4") (pinfunction "E_4") (pintype "passive"))
      (node (ref "Q12") (pin "2") (pinfunction "S_2") (pintype "passive"))
      (node (ref "R13") (pin "1") (pinfunction "1_1") (pintype "passive"))
      (node (ref "R14") (pin "1") (pinfunction "1_1") (pintype "passive"))
      (node (ref "R18") (pin "1") (pinfunction "1_1") (pintype "passive"))
      (node (ref "R31") (pin "1") (pinfunction "1_1") (pintype "passive"))
      (node (ref "R70") (pin "2") (pinfunction "2_2") (pintype "passive"))
      (node (ref "R96") (pin "2") (pinfunction "2_2") (pintype "passive"))
      (node (ref "U11") (pin "8") (pinfunction "VCC_8") (pintype "bidirectional"))
      (node (ref "U12") (pin "5") (pinfunction "OUT_5") (pintype "bidirectional"))
      (node (ref "U5") (pin "1") (pinfunction "VDD_IO_1") (pintype "bidirectional"))
      (node (ref "U5") (pin "14") (pinfunction "VDD_14") (pintype "bidirectional"))
      (node (ref "U5") (pin "8") (pinfunction "CS_8") (pintype "bidirectional"))
      (node (ref "U8") (pin "1-1") (pinfunction "1_1-1") (pintype "bidirectional"))
      (node (ref "U8") (pin "1-2") (pinfunction "1_1-2") (pintype "bidirectional"))
      (node (ref "U9") (pin "5") (pinfunction "VCC_5") (pintype "bidirectional"))
    )
    (net (code "176") (name "XIN") (class "Default")
      (node (ref "R8") (pin "1") (pinfunction "1_1") (pintype "passive"))
      (node (ref "U1") (pin "A15") (pinfunction "PB22/I6/SERCOM1+5.2/TC7.0/QDI.2_A15") (pintype "bidirectional"))
    )
    (net (code "177") (name "XOUT") (class "Default")
      (node (ref "C51") (pin "1") (pinfunction "1_1") (pintype "passive"))
      (node (ref "U1") (pin "A14") (pinfunction "PB23/I7/SERCOM1+5.3/TC7.1/QDI.0_A14") (pintype "bidirectional"))
      (node (ref "X4") (pin "3") (pinfunction "X2_3") (pintype "bidirectional"))
    )
    (net (code "178") (name "unconnected-(J3-Pad5)") (class "Default")
      (node (ref "J3") (pin "5") (pinfunction "5_5") (pintype "bidirectional"))
    )
    (net (code "179") (name "unconnected-(J3-Pad7)") (class "Default")
      (node (ref "J3") (pin "7") (pinfunction "7_7") (pintype "bidirectional"))
    )
    (net (code "180") (name "unconnected-(J4-PadSS1)") (class "Default")
      (node (ref "J4") (pin "SS1") (pinfunction "SS1_SS1") (pintype "bidirectional"))
    )
    (net (code "181") (name "unconnected-(J4-PadSS2)") (class "Default")
      (node (ref "J4") (pin "SS2") (pinfunction "SS2_SS2") (pintype "bidirectional"))
    )
    (net (code "182") (name "unconnected-(J5-PadSS1)") (class "Default")
      (node (ref "J5") (pin "SS1") (pinfunction "SS1_SS1") (pintype "bidirectional"))
    )
    (net (code "183") (name "unconnected-(J5-PadSS2)") (class "Default")
      (node (ref "J5") (pin "SS2") (pinfunction "SS2_SS2") (pintype "bidirectional"))
    )
    (net (code "184") (name "unconnected-(J6-Pad14)") (class "Default")
      (node (ref "J6") (pin "14") (pinfunction "14_14") (pintype "bidirectional"))
    )
    (net (code "185") (name "unconnected-(U1B-PA23{slash}I2C{slash}I7{slash}SERCOM3.1+5.0{slash}SOF{slash}I2SFS1{slash}TC4.1+TCC1.7+0.3{slash}PTC-PadC14)") (class "Default")
      (node (ref "U1") (pin "C14") (pinfunction "PA23/I2C/I7/SERCOM3.1+5.0/SOF/I2SFS1/TC4.1+TCC1.7+0.3/PTC_C14") (pintype "bidirectional"))
    )
    (net (code "186") (name "unconnected-(U1B-PB15{slash}I15{slash}SERCOM4.3{slash}PCC9{slash}TC5.1{slash}TCC4.1+0.3{slash}PTC-PadP7)") (class "Default")
      (node (ref "U1") (pin "P7") (pinfunction "PB15/I15/SERCOM4.3/PCC9/TC5.1/TCC4.1+0.3/PTC_P7") (pintype "bidirectional"))
    )
    (net (code "187") (name "unconnected-(U5-ADC1-Pad16)") (class "Default")
      (node (ref "U5") (pin "16") (pinfunction "ADC1_16") (pintype "bidirectional"))
    )
    (net (code "188") (name "unconnected-(U5-ADC2-Pad15)") (class "Default")
      (node (ref "U5") (pin "15") (pinfunction "ADC2_15") (pintype "bidirectional"))
    )
    (net (code "189") (name "unconnected-(U5-ADC3-Pad13)") (class "Default")
      (node (ref "U5") (pin "13") (pinfunction "ADC3_13") (pintype "bidirectional"))
    )
    (net (code "190") (name "unconnected-(U5-INT2-Pad9)") (class "Default")
      (node (ref "U5") (pin "9") (pinfunction "INT2_9") (pintype "bidirectional"))
    )
    (net (code "191") (name "unconnected-(U5-NC-Pad2)") (class "Default")
      (node (ref "U5") (pin "2") (pinfunction "NC_2") (pintype "bidirectional"))
    )
    (net (code "192") (name "unconnected-(U5-NC-Pad3)") (class "Default")
      (node (ref "U5") (pin "3") (pinfunction "NC_3") (pintype "bidirectional"))
    )
    (net (code "193") (name "unconnected-(U10-Pad4)") (class "Default")
      (node (ref "U10") (pin "4") (pinfunction "4_4") (pintype "bidirectional"))
    )
    (net (code "194") (name "unconnected-(U10-Pad5)") (class "Default")
      (node (ref "U10") (pin "5") (pinfunction "5_5") (pintype "bidirectional"))
    )
    (net (code "195") (name "unconnected-(U10-Pad6)") (class "Default")
      (node (ref "U10") (pin "6") (pinfunction "6_6") (pintype "bidirectional"))
    )
    (net (code "196") (name "unconnected-(U10-Pad11)") (class "Default")
      (node (ref "U10") (pin "11") (pinfunction "11_11") (pintype "bidirectional"))
    )
    (net (code "197") (name "unconnected-(U10-Pad12)") (class "Default")
      (node (ref "U10") (pin "12") (pinfunction "12_12") (pintype "bidirectional"))
    )
    (net (code "198") (name "unconnected-(U10-Pad13)") (class "Default")
      (node (ref "U10") (pin "13") (pinfunction "13_13") (pintype "bidirectional"))
    )
    (net (code "199") (name "unconnected-(U10-Pad14)") (class "Default")
      (node (ref "U10") (pin "14") (pinfunction "14_14") (pintype "bidirectional"))
    )
    (net (code "200") (name "unconnected-(U10-Pad17)") (class "Default")
      (node (ref "U10") (pin "17") (pinfunction "17_17") (pintype "bidirectional"))
    )
    (net (code "201") (name "unconnected-(U10-Pad18)") (class "Default")
      (node (ref "U10") (pin "18") (pinfunction "18_18") (pintype "bidirectional"))
    )
    (net (code "202") (name "unconnected-(U10-Pad19)") (class "Default")
      (node (ref "U10") (pin "19") (pinfunction "19_19") (pintype "bidirectional"))
    )
    (net (code "203") (name "unconnected-(U10-Pad20)") (class "Default")
      (node (ref "U10") (pin "20") (pinfunction "20_20") (pintype "bidirectional"))
    )
    (net (code "204") (name "unconnected-(U10-Pad27)") (class "Default")
      (node (ref "U10") (pin "27") (pinfunction "27_27") (pintype "bidirectional"))
    )
    (net (code "205") (name "unconnected-(U10-Pad28)") (class "Default")
      (node (ref "U10") (pin "28") (pinfunction "28_28") (pintype "bidirectional"))
    )
    (net (code "206") (name "unconnected-(U10-Pad29)") (class "Default")
      (node (ref "U10") (pin "29") (pinfunction "29_29") (pintype "bidirectional"))
    )
    (net (code "207") (name "unconnected-(U11-NC-Pad1)") (class "Default")
      (node (ref "U11") (pin "1") (pinfunction "NC_1") (pintype "bidirectional"))
    )
    (net (code "208") (name "unconnected-(U11-NC-Pad2)") (class "Default")
      (node (ref "U11") (pin "2") (pinfunction "NC_2") (pintype "bidirectional"))
    )
    (net (code "209") (name "unconnected-(U11-NC-Pad3)") (class "Default")
      (node (ref "U11") (pin "3") (pinfunction "NC_3") (pintype "bidirectional"))
    )
    (net (code "210") (name "unconnected-(U11-NC-Pad7)") (class "Default")
      (node (ref "U11") (pin "7") (pinfunction "NC_7") (pintype "bidirectional"))
    )
    (net (code "211") (name "unconnected-(U12-PG-Pad1)") (class "Default")
      (node (ref "U12") (pin "1") (pinfunction "PG_1") (pintype "bidirectional"))
    )
    (net (code "212") (name "unconnected-(U13-NC{slash}ADJ-Pad4)") (class "Default")
      (node (ref "U13") (pin "4") (pinfunction "NC/ADJ_4") (pintype "bidirectional"))
    )
    (net (code "213") (name "unconnected-(USB1-A8{slash}SBU1-PadA8)") (class "Default")
      (node (ref "USB1") (pin "A8") (pinfunction "A8/SBU1_A8") (pintype "bidirectional"))
    )
    (net (code "214") (name "unconnected-(USB1-B8{slash}SBU2-PadB8)") (class "Default")
      (node (ref "USB1") (pin "B8") (pinfunction "B8/SBU2_B8") (pintype "bidirectional"))
    )
  )
)
